# Amplifiers_DAC.net
KiCad netlist of a schematic drawn in Altium Designer
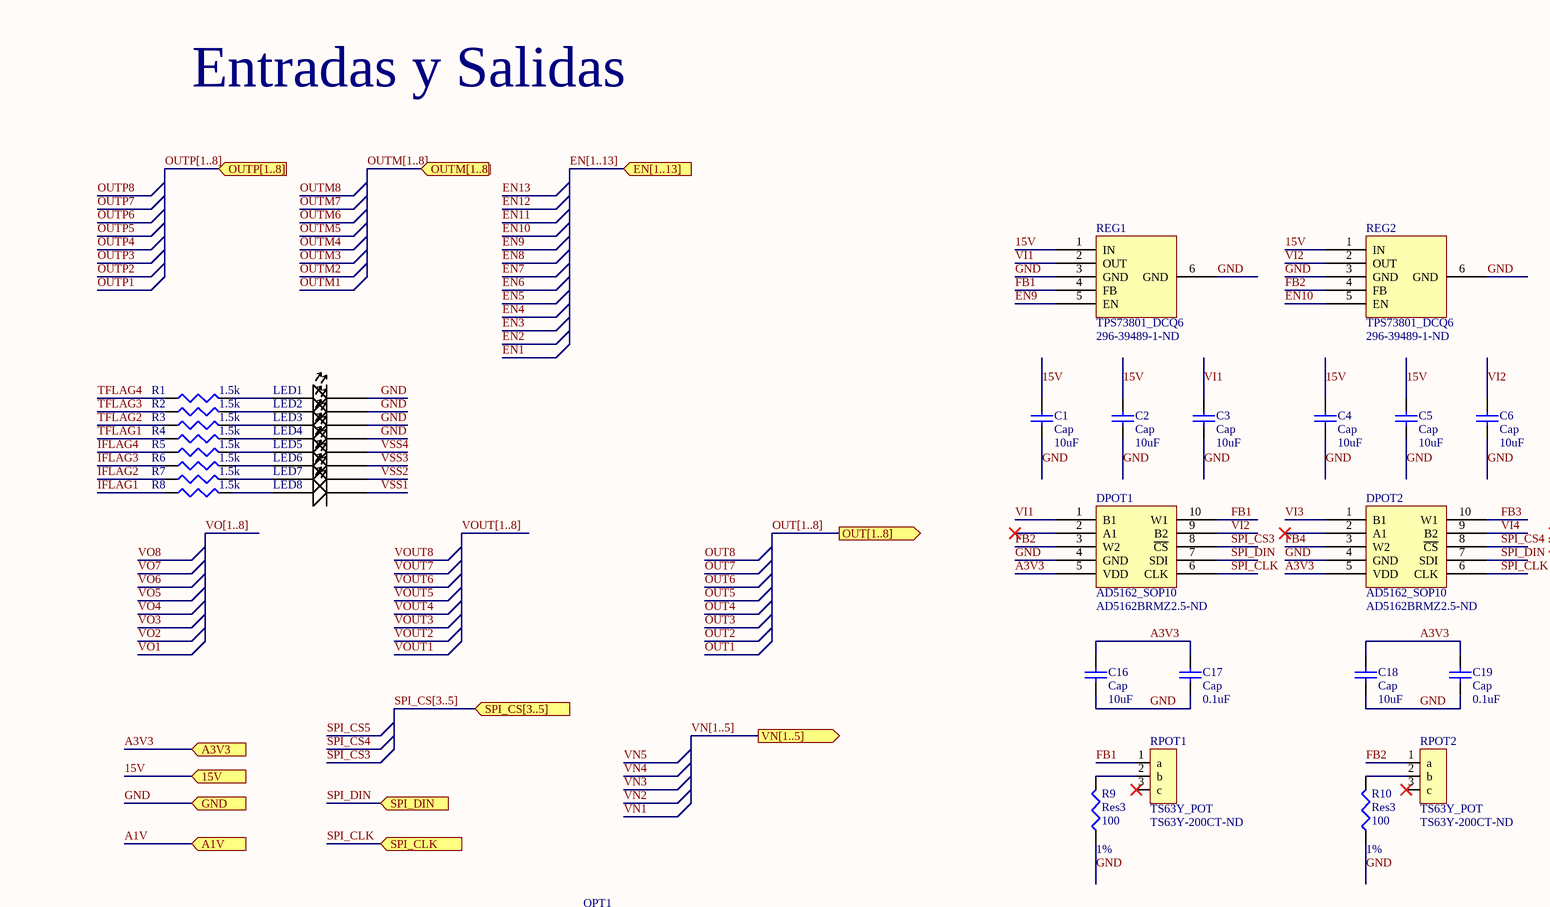
[diagram p0: Amplifiers_DAC.SchDoc, top left]
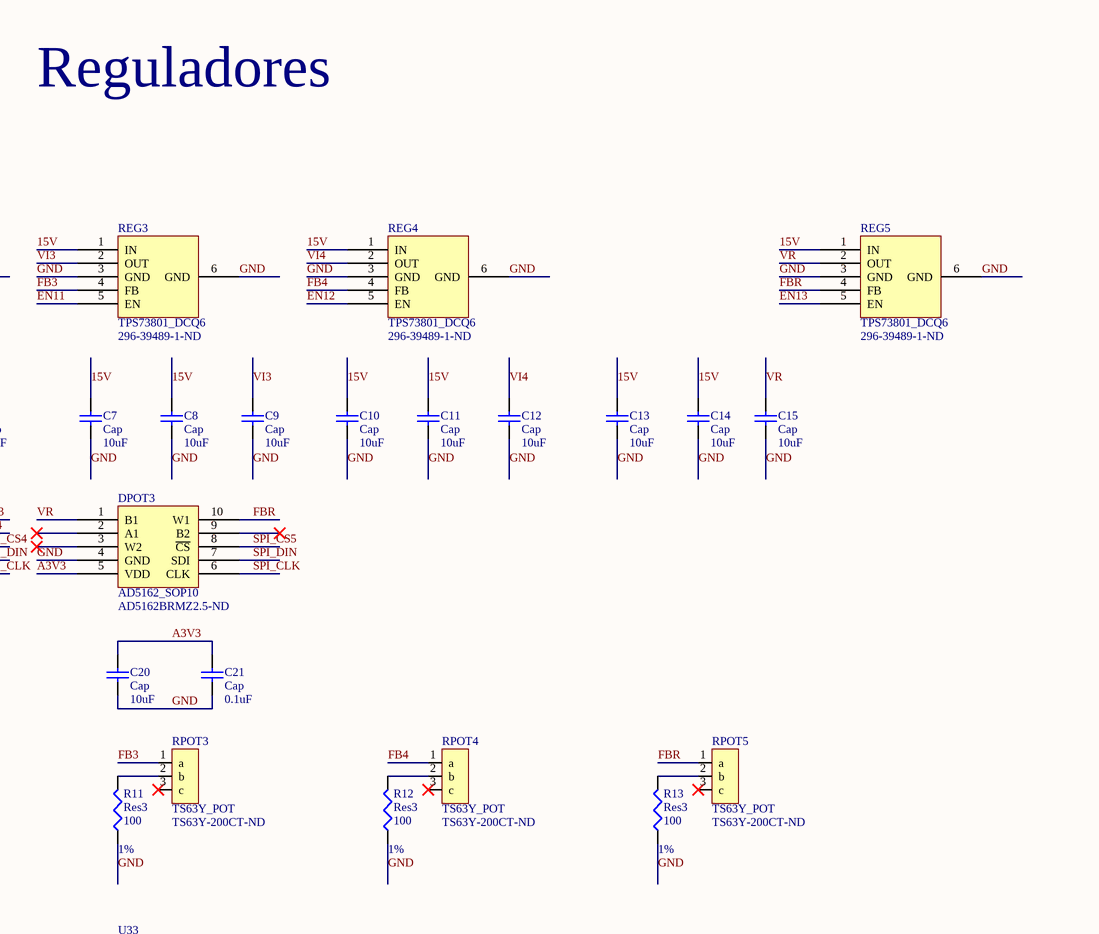
[diagram p1: Amplifiers_DAC.SchDoc, top right]
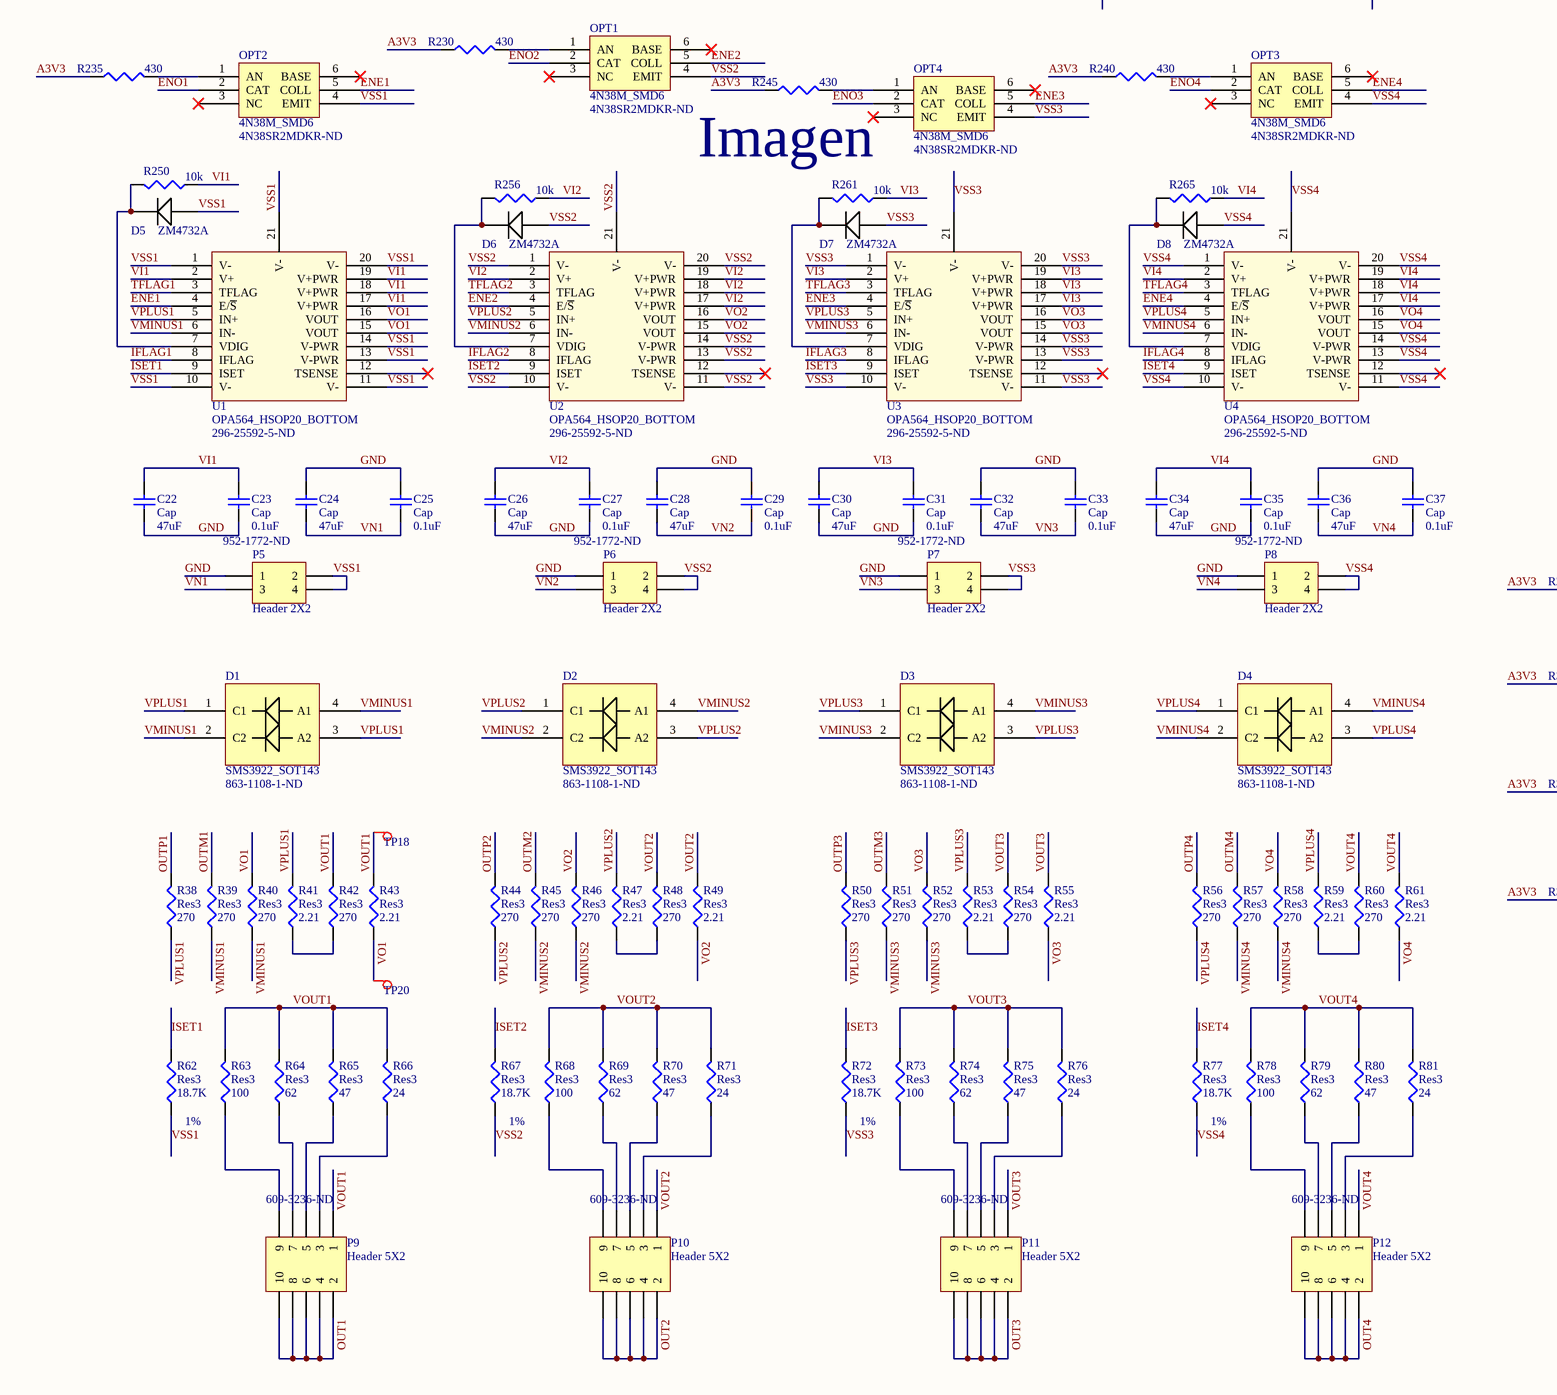
[diagram p2: Amplifiers_DAC.SchDoc, bottom left]
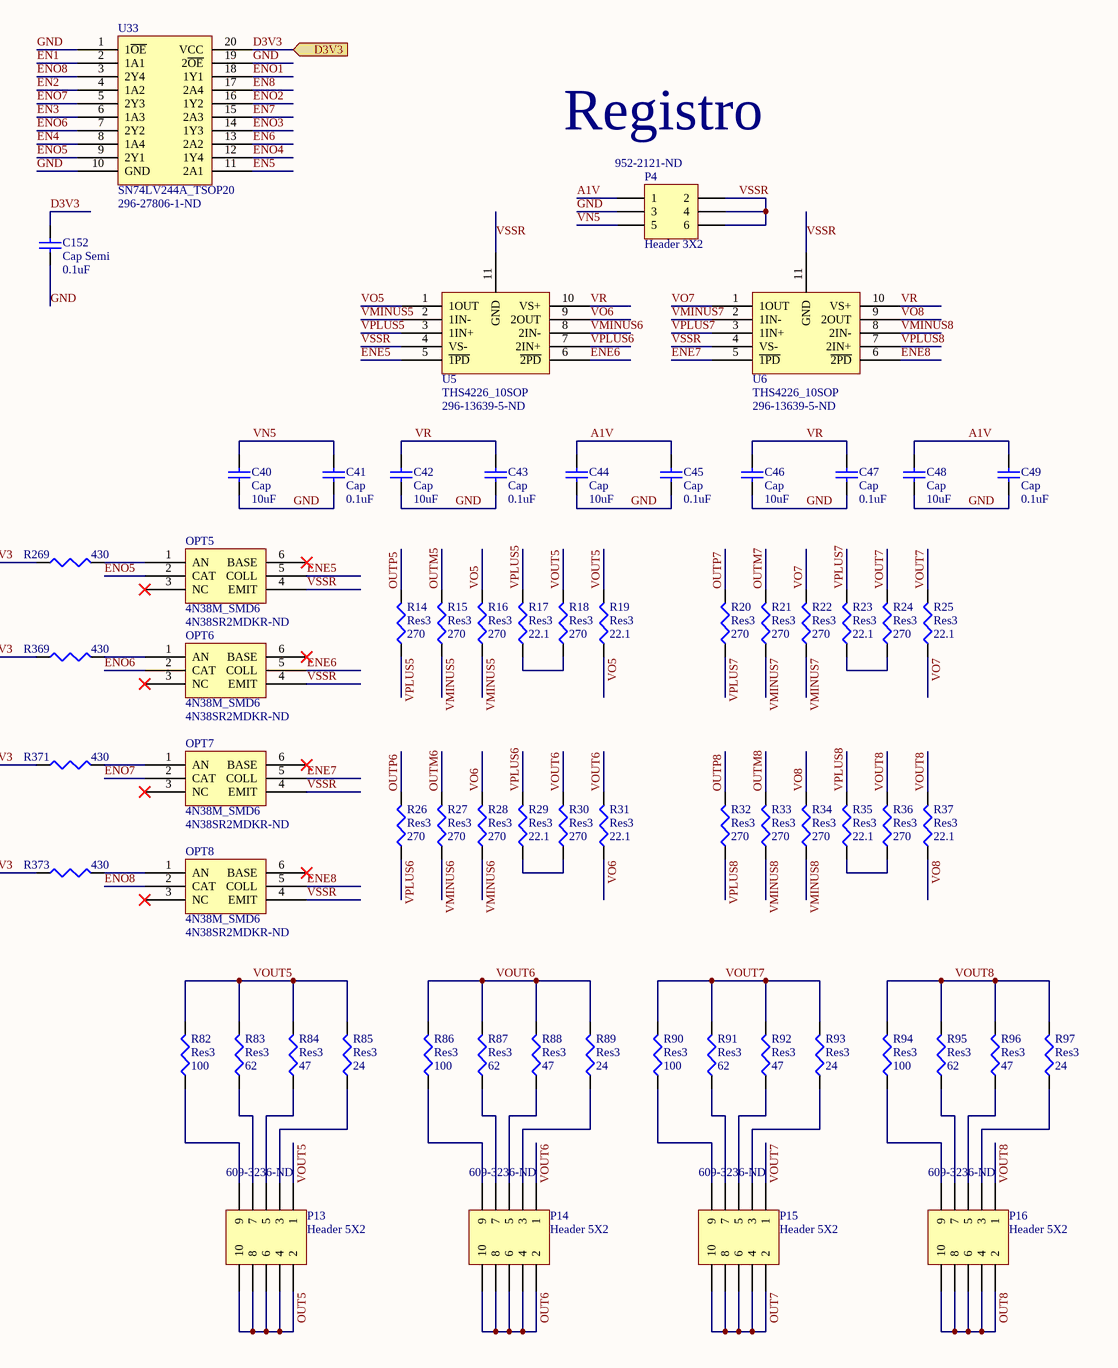
[diagram p3: Amplifiers_DAC.SchDoc, bottom right]

(export (version "E")
  (design (tool "Eeschema 10.0.6"))
  (components
    (comp (ref "C1")
      (value "Cap")
      (footprint "RES_0805")
      (description "Capacitor (Semiconductor SIM Model)")
      (fields (field (name "ALTIUM_VALUE") "10uF") (field (name "PUBLISHER") "Altium Limited"))
      (libsource (lib "Miscellaneous Devices") (part "Cap Semi"))
    )
    (comp (ref "C2")
      (value "Cap")
      (footprint "RES_0805")
      (description "Capacitor (Semiconductor SIM Model)")
      (fields (field (name "ALTIUM_VALUE") "10uF") (field (name "PUBLISHER") "Altium Limited"))
      (libsource (lib "Miscellaneous Devices") (part "Cap Semi"))
    )
    (comp (ref "C3")
      (value "Cap")
      (footprint "RES_0805")
      (description "Capacitor (Semiconductor SIM Model)")
      (fields (field (name "ALTIUM_VALUE") "10uF") (field (name "PUBLISHER") "Altium Limited"))
      (libsource (lib "Miscellaneous Devices") (part "Cap Semi"))
    )
    (comp (ref "C4")
      (value "Cap")
      (footprint "RES_0805")
      (description "Capacitor (Semiconductor SIM Model)")
      (fields (field (name "ALTIUM_VALUE") "10uF") (field (name "PUBLISHER") "Altium Limited"))
      (libsource (lib "Miscellaneous Devices") (part "Cap Semi"))
    )
    (comp (ref "C5")
      (value "Cap")
      (footprint "RES_0805")
      (description "Capacitor (Semiconductor SIM Model)")
      (fields (field (name "ALTIUM_VALUE") "10uF") (field (name "PUBLISHER") "Altium Limited"))
      (libsource (lib "Miscellaneous Devices") (part "Cap Semi"))
    )
    (comp (ref "C6")
      (value "Cap")
      (footprint "RES_0805")
      (description "Capacitor (Semiconductor SIM Model)")
      (fields (field (name "ALTIUM_VALUE") "10uF") (field (name "PUBLISHER") "Altium Limited"))
      (libsource (lib "Miscellaneous Devices") (part "Cap Semi"))
    )
    (comp (ref "C7")
      (value "Cap")
      (footprint "RES_0805")
      (description "Capacitor (Semiconductor SIM Model)")
      (fields (field (name "ALTIUM_VALUE") "10uF") (field (name "PUBLISHER") "Altium Limited"))
      (libsource (lib "Miscellaneous Devices") (part "Cap Semi"))
    )
    (comp (ref "C8")
      (value "Cap")
      (footprint "RES_0805")
      (description "Capacitor (Semiconductor SIM Model)")
      (fields (field (name "ALTIUM_VALUE") "10uF") (field (name "PUBLISHER") "Altium Limited"))
      (libsource (lib "Miscellaneous Devices") (part "Cap Semi"))
    )
    (comp (ref "C9")
      (value "Cap")
      (footprint "RES_0805")
      (description "Capacitor (Semiconductor SIM Model)")
      (fields (field (name "ALTIUM_VALUE") "10uF") (field (name "PUBLISHER") "Altium Limited"))
      (libsource (lib "Miscellaneous Devices") (part "Cap Semi"))
    )
    (comp (ref "C10")
      (value "Cap")
      (footprint "RES_0805")
      (description "Capacitor (Semiconductor SIM Model)")
      (fields (field (name "ALTIUM_VALUE") "10uF") (field (name "PUBLISHER") "Altium Limited"))
      (libsource (lib "Miscellaneous Devices") (part "Cap Semi"))
    )
    (comp (ref "C11")
      (value "Cap")
      (footprint "RES_0805")
      (description "Capacitor (Semiconductor SIM Model)")
      (fields (field (name "ALTIUM_VALUE") "10uF") (field (name "PUBLISHER") "Altium Limited"))
      (libsource (lib "Miscellaneous Devices") (part "Cap Semi"))
    )
    (comp (ref "C12")
      (value "Cap")
      (footprint "RES_0805")
      (description "Capacitor (Semiconductor SIM Model)")
      (fields (field (name "ALTIUM_VALUE") "10uF") (field (name "PUBLISHER") "Altium Limited"))
      (libsource (lib "Miscellaneous Devices") (part "Cap Semi"))
    )
    (comp (ref "C13")
      (value "Cap")
      (footprint "RES_0805")
      (description "Capacitor (Semiconductor SIM Model)")
      (fields (field (name "ALTIUM_VALUE") "10uF") (field (name "PUBLISHER") "Altium Limited"))
      (libsource (lib "Miscellaneous Devices") (part "Cap Semi"))
    )
    (comp (ref "C14")
      (value "Cap")
      (footprint "RES_0805")
      (description "Capacitor (Semiconductor SIM Model)")
      (fields (field (name "ALTIUM_VALUE") "10uF") (field (name "PUBLISHER") "Altium Limited"))
      (libsource (lib "Miscellaneous Devices") (part "Cap Semi"))
    )
    (comp (ref "C15")
      (value "Cap")
      (footprint "RES_0805")
      (description "Capacitor (Semiconductor SIM Model)")
      (fields (field (name "ALTIUM_VALUE") "10uF") (field (name "PUBLISHER") "Altium Limited"))
      (libsource (lib "Miscellaneous Devices") (part "Cap Semi"))
    )
    (comp (ref "C16")
      (value "Cap")
      (footprint "RES_0805")
      (description "Capacitor (Semiconductor SIM Model)")
      (fields (field (name "ALTIUM_VALUE") "10uF") (field (name "PUBLISHER") "Altium Limited"))
      (libsource (lib "Miscellaneous Devices") (part "Cap Semi"))
    )
    (comp (ref "C17")
      (value "Cap")
      (footprint "J1-0603")
      (description "Capacitor (Semiconductor SIM Model)")
      (fields (field (name "ALTIUM_VALUE") "0.1uF") (field (name "PUBLISHER") "Altium Limited"))
      (libsource (lib "Miscellaneous Devices") (part "Cap Semi"))
    )
    (comp (ref "C18")
      (value "Cap")
      (footprint "RES_0805")
      (description "Capacitor (Semiconductor SIM Model)")
      (fields (field (name "ALTIUM_VALUE") "10uF") (field (name "PUBLISHER") "Altium Limited"))
      (libsource (lib "Miscellaneous Devices") (part "Cap Semi"))
    )
    (comp (ref "C19")
      (value "Cap")
      (footprint "J1-0603")
      (description "Capacitor (Semiconductor SIM Model)")
      (fields (field (name "ALTIUM_VALUE") "0.1uF") (field (name "PUBLISHER") "Altium Limited"))
      (libsource (lib "Miscellaneous Devices") (part "Cap Semi"))
    )
    (comp (ref "C20")
      (value "Cap")
      (footprint "RES_0805")
      (description "Capacitor (Semiconductor SIM Model)")
      (fields (field (name "ALTIUM_VALUE") "10uF") (field (name "PUBLISHER") "Altium Limited"))
      (libsource (lib "Miscellaneous Devices") (part "Cap Semi"))
    )
    (comp (ref "C21")
      (value "Cap")
      (footprint "J1-0603")
      (description "Capacitor (Semiconductor SIM Model)")
      (fields (field (name "ALTIUM_VALUE") "0.1uF") (field (name "PUBLISHER") "Altium Limited"))
      (libsource (lib "Miscellaneous Devices") (part "Cap Semi"))
    )
    (comp (ref "C22")
      (value "Cap")
      (footprint "RES_1206")
      (description "Capacitor (Semiconductor SIM Model)")
      (fields (field (name "ALTIUM_VALUE") "47uF") (field (name "PUBLISHER") "Altium Limited"))
      (libsource (lib "Miscellaneous Devices") (part "Cap Semi"))
    )
    (comp (ref "C23")
      (value "Cap")
      (footprint "J1-0603")
      (description "Capacitor (Semiconductor SIM Model)")
      (fields (field (name "ALTIUM_VALUE") "0.1uF") (field (name "PUBLISHER") "Altium Limited"))
      (libsource (lib "Miscellaneous Devices") (part "Cap Semi"))
    )
    (comp (ref "C24")
      (value "Cap")
      (footprint "RES_1206")
      (description "Capacitor (Semiconductor SIM Model)")
      (fields (field (name "ALTIUM_VALUE") "47uF") (field (name "PUBLISHER") "Altium Limited"))
      (libsource (lib "Miscellaneous Devices") (part "Cap Semi"))
    )
    (comp (ref "C25")
      (value "Cap")
      (footprint "J1-0603")
      (description "Capacitor (Semiconductor SIM Model)")
      (fields (field (name "ALTIUM_VALUE") "0.1uF") (field (name "PUBLISHER") "Altium Limited"))
      (libsource (lib "Miscellaneous Devices") (part "Cap Semi"))
    )
    (comp (ref "C26")
      (value "Cap")
      (footprint "RES_1206")
      (description "Capacitor (Semiconductor SIM Model)")
      (fields (field (name "ALTIUM_VALUE") "47uF") (field (name "PUBLISHER") "Altium Limited"))
      (libsource (lib "Miscellaneous Devices") (part "Cap Semi"))
    )
    (comp (ref "C27")
      (value "Cap")
      (footprint "J1-0603")
      (description "Capacitor (Semiconductor SIM Model)")
      (fields (field (name "ALTIUM_VALUE") "0.1uF") (field (name "PUBLISHER") "Altium Limited"))
      (libsource (lib "Miscellaneous Devices") (part "Cap Semi"))
    )
    (comp (ref "C28")
      (value "Cap")
      (footprint "RES_1206")
      (description "Capacitor (Semiconductor SIM Model)")
      (fields (field (name "ALTIUM_VALUE") "47uF") (field (name "PUBLISHER") "Altium Limited"))
      (libsource (lib "Miscellaneous Devices") (part "Cap Semi"))
    )
    (comp (ref "C29")
      (value "Cap")
      (footprint "J1-0603")
      (description "Capacitor (Semiconductor SIM Model)")
      (fields (field (name "ALTIUM_VALUE") "0.1uF") (field (name "PUBLISHER") "Altium Limited"))
      (libsource (lib "Miscellaneous Devices") (part "Cap Semi"))
    )
    (comp (ref "C30")
      (value "Cap")
      (footprint "RES_1206")
      (description "Capacitor (Semiconductor SIM Model)")
      (fields (field (name "ALTIUM_VALUE") "47uF") (field (name "PUBLISHER") "Altium Limited"))
      (libsource (lib "Miscellaneous Devices") (part "Cap Semi"))
    )
    (comp (ref "C31")
      (value "Cap")
      (footprint "J1-0603")
      (description "Capacitor (Semiconductor SIM Model)")
      (fields (field (name "ALTIUM_VALUE") "0.1uF") (field (name "PUBLISHER") "Altium Limited"))
      (libsource (lib "Miscellaneous Devices") (part "Cap Semi"))
    )
    (comp (ref "C32")
      (value "Cap")
      (footprint "RES_1206")
      (description "Capacitor (Semiconductor SIM Model)")
      (fields (field (name "ALTIUM_VALUE") "47uF") (field (name "PUBLISHER") "Altium Limited"))
      (libsource (lib "Miscellaneous Devices") (part "Cap Semi"))
    )
    (comp (ref "C33")
      (value "Cap")
      (footprint "J1-0603")
      (description "Capacitor (Semiconductor SIM Model)")
      (fields (field (name "ALTIUM_VALUE") "0.1uF") (field (name "PUBLISHER") "Altium Limited"))
      (libsource (lib "Miscellaneous Devices") (part "Cap Semi"))
    )
    (comp (ref "C34")
      (value "Cap")
      (footprint "RES_1206")
      (description "Capacitor (Semiconductor SIM Model)")
      (fields (field (name "ALTIUM_VALUE") "47uF") (field (name "PUBLISHER") "Altium Limited"))
      (libsource (lib "Miscellaneous Devices") (part "Cap Semi"))
    )
    (comp (ref "C35")
      (value "Cap")
      (footprint "J1-0603")
      (description "Capacitor (Semiconductor SIM Model)")
      (fields (field (name "ALTIUM_VALUE") "0.1uF") (field (name "PUBLISHER") "Altium Limited"))
      (libsource (lib "Miscellaneous Devices") (part "Cap Semi"))
    )
    (comp (ref "C36")
      (value "Cap")
      (footprint "RES_1206")
      (description "Capacitor (Semiconductor SIM Model)")
      (fields (field (name "ALTIUM_VALUE") "47uF") (field (name "PUBLISHER") "Altium Limited"))
      (libsource (lib "Miscellaneous Devices") (part "Cap Semi"))
    )
    (comp (ref "C37")
      (value "Cap")
      (footprint "J1-0603")
      (description "Capacitor (Semiconductor SIM Model)")
      (fields (field (name "ALTIUM_VALUE") "0.1uF") (field (name "PUBLISHER") "Altium Limited"))
      (libsource (lib "Miscellaneous Devices") (part "Cap Semi"))
    )
    (comp (ref "C40")
      (value "Cap")
      (footprint "RES_0805")
      (description "Capacitor (Semiconductor SIM Model)")
      (fields (field (name "ALTIUM_VALUE") "10uF") (field (name "PUBLISHER") "Altium Limited"))
      (libsource (lib "Miscellaneous Devices") (part "Cap Semi"))
    )
    (comp (ref "C41")
      (value "Cap")
      (footprint "J1-0603")
      (description "Capacitor (Semiconductor SIM Model)")
      (fields (field (name "ALTIUM_VALUE") "0.1uF") (field (name "PUBLISHER") "Altium Limited"))
      (libsource (lib "Miscellaneous Devices") (part "Cap Semi"))
    )
    (comp (ref "C42")
      (value "Cap")
      (footprint "RES_0805")
      (description "Capacitor (Semiconductor SIM Model)")
      (fields (field (name "ALTIUM_VALUE") "10uF") (field (name "PUBLISHER") "Altium Limited"))
      (libsource (lib "Miscellaneous Devices") (part "Cap Semi"))
    )
    (comp (ref "C43")
      (value "Cap")
      (footprint "J1-0603")
      (description "Capacitor (Semiconductor SIM Model)")
      (fields (field (name "ALTIUM_VALUE") "0.1uF") (field (name "PUBLISHER") "Altium Limited"))
      (libsource (lib "Miscellaneous Devices") (part "Cap Semi"))
    )
    (comp (ref "C44")
      (value "Cap")
      (footprint "RES_0805")
      (description "Capacitor (Semiconductor SIM Model)")
      (fields (field (name "ALTIUM_VALUE") "10uF") (field (name "PUBLISHER") "Altium Limited"))
      (libsource (lib "Miscellaneous Devices") (part "Cap Semi"))
    )
    (comp (ref "C45")
      (value "Cap")
      (footprint "J1-0603")
      (description "Capacitor (Semiconductor SIM Model)")
      (fields (field (name "ALTIUM_VALUE") "0.1uF") (field (name "PUBLISHER") "Altium Limited"))
      (libsource (lib "Miscellaneous Devices") (part "Cap Semi"))
    )
    (comp (ref "C46")
      (value "Cap")
      (footprint "RES_0805")
      (description "Capacitor (Semiconductor SIM Model)")
      (fields (field (name "ALTIUM_VALUE") "10uF") (field (name "PUBLISHER") "Altium Limited"))
      (libsource (lib "Miscellaneous Devices") (part "Cap Semi"))
    )
    (comp (ref "C47")
      (value "Cap")
      (footprint "J1-0603")
      (description "Capacitor (Semiconductor SIM Model)")
      (fields (field (name "ALTIUM_VALUE") "0.1uF") (field (name "PUBLISHER") "Altium Limited"))
      (libsource (lib "Miscellaneous Devices") (part "Cap Semi"))
    )
    (comp (ref "C48")
      (value "Cap")
      (footprint "RES_0805")
      (description "Capacitor (Semiconductor SIM Model)")
      (fields (field (name "ALTIUM_VALUE") "10uF") (field (name "PUBLISHER") "Altium Limited"))
      (libsource (lib "Miscellaneous Devices") (part "Cap Semi"))
    )
    (comp (ref "C49")
      (value "Cap")
      (footprint "J1-0603")
      (description "Capacitor (Semiconductor SIM Model)")
      (fields (field (name "ALTIUM_VALUE") "0.1uF") (field (name "PUBLISHER") "Altium Limited"))
      (libsource (lib "Miscellaneous Devices") (part "Cap Semi"))
    )
    (comp (ref "C152")
      (value "Cap Semi")
      (footprint "J1-0603")
      (description "Capacitor (Semiconductor SIM Model)")
      (fields (field (name "ALTIUM_VALUE") "0.1uF") (field (name "PUBLISHER") "Altium Limited"))
      (libsource (lib "Miscellaneous Devices") (part "Cap Semi"))
    )
    (comp (ref "D1")
      (value "SMS3922_SOT143")
      (footprint "SMS3922_SOT143")
      (fields (field (name "SUPPLIER PART NUMBER 1") "863-1108-1-ND"))
      (libsource (lib "Lib1") (part "SMS3922_SOT143"))
    )
    (comp (ref "D2")
      (value "SMS3922_SOT143")
      (footprint "SMS3922_SOT143")
      (fields (field (name "SUPPLIER PART NUMBER 1") "863-1108-1-ND"))
      (libsource (lib "Lib1") (part "SMS3922_SOT143"))
    )
    (comp (ref "D3")
      (value "SMS3922_SOT143")
      (footprint "SMS3922_SOT143")
      (fields (field (name "SUPPLIER PART NUMBER 1") "863-1108-1-ND"))
      (libsource (lib "Lib1") (part "SMS3922_SOT143"))
    )
    (comp (ref "D4")
      (value "SMS3922_SOT143")
      (footprint "SMS3922_SOT143")
      (fields (field (name "SUPPLIER PART NUMBER 1") "863-1108-1-ND"))
      (libsource (lib "Lib1") (part "SMS3922_SOT143"))
    )
    (comp (ref "D5") (value "ZM4732A") (footprint "ZM4732A") (libsource (lib "Lib1") (part "ZM4732A")))
    (comp (ref "D6") (value "ZM4732A") (footprint "ZM4732A") (libsource (lib "Lib1") (part "ZM4732A")))
    (comp (ref "D7") (value "ZM4732A") (footprint "ZM4732A") (libsource (lib "Lib1") (part "ZM4732A")))
    (comp (ref "D8") (value "ZM4732A") (footprint "ZM4732A") (libsource (lib "Lib1") (part "ZM4732A")))
    (comp (ref "DPOT1")
      (value "AD5162_SOP10")
      (footprint "AD5162_SOP10")
      (fields (field (name "SUPPLIER PART NUMBER 1") "AD5162BRMZ2.5-ND"))
      (libsource (lib "Lib1") (part "AD5162_SOP10"))
    )
    (comp (ref "DPOT2")
      (value "AD5162_SOP10")
      (footprint "AD5162_SOP10")
      (fields (field (name "SUPPLIER PART NUMBER 1") "AD5162BRMZ2.5-ND"))
      (libsource (lib "Lib1") (part "AD5162_SOP10"))
    )
    (comp (ref "DPOT3")
      (value "AD5162_SOP10")
      (footprint "AD5162_SOP10")
      (fields (field (name "SUPPLIER PART NUMBER 1") "AD5162BRMZ2.5-ND"))
      (libsource (lib "Lib1") (part "AD5162_SOP10"))
    )
    (comp (ref "LED1") (value "LED") (footprint "LED") (libsource (lib "Lib1") (part "LED")))
    (comp (ref "LED2") (value "LED") (footprint "LED") (libsource (lib "Lib1") (part "LED")))
    (comp (ref "LED3") (value "LED") (footprint "LED") (libsource (lib "Lib1") (part "LED")))
    (comp (ref "LED4") (value "LED") (footprint "LED") (libsource (lib "Lib1") (part "LED")))
    (comp (ref "LED5") (value "LED") (footprint "LED") (libsource (lib "Lib1") (part "LED")))
    (comp (ref "LED6") (value "LED") (footprint "LED") (libsource (lib "Lib1") (part "LED")))
    (comp (ref "LED7") (value "LED") (footprint "LED") (libsource (lib "Lib1") (part "LED")))
    (comp (ref "LED8") (value "LED") (footprint "LED") (libsource (lib "Lib1") (part "LED")))
    (comp (ref "OPT1")
      (value "4N38M_SMD6")
      (footprint "4N38M_SMD6")
      (fields (field (name "SUPPLIER PART NUMBER 1") "4N38SR2MDKR-ND"))
      (libsource (lib "Lib1") (part "4N38M_SMD6"))
    )
    (comp (ref "OPT2")
      (value "4N38M_SMD6")
      (footprint "4N38M_SMD6")
      (fields (field (name "SUPPLIER PART NUMBER 1") "4N38SR2MDKR-ND"))
      (libsource (lib "Lib1") (part "4N38M_SMD6"))
    )
    (comp (ref "OPT3")
      (value "4N38M_SMD6")
      (footprint "4N38M_SMD6")
      (fields (field (name "SUPPLIER PART NUMBER 1") "4N38SR2MDKR-ND"))
      (libsource (lib "Lib1") (part "4N38M_SMD6"))
    )
    (comp (ref "OPT4")
      (value "4N38M_SMD6")
      (footprint "4N38M_SMD6")
      (fields (field (name "SUPPLIER PART NUMBER 1") "4N38SR2MDKR-ND"))
      (libsource (lib "Lib1") (part "4N38M_SMD6"))
    )
    (comp (ref "OPT5")
      (value "4N38M_SMD6")
      (footprint "4N38M_SMD6")
      (fields (field (name "SUPPLIER PART NUMBER 1") "4N38SR2MDKR-ND"))
      (libsource (lib "Lib1") (part "4N38M_SMD6"))
    )
    (comp (ref "OPT6")
      (value "4N38M_SMD6")
      (footprint "4N38M_SMD6")
      (fields (field (name "SUPPLIER PART NUMBER 1") "4N38SR2MDKR-ND"))
      (libsource (lib "Lib1") (part "4N38M_SMD6"))
    )
    (comp (ref "OPT7")
      (value "4N38M_SMD6")
      (footprint "4N38M_SMD6")
      (fields (field (name "SUPPLIER PART NUMBER 1") "4N38SR2MDKR-ND"))
      (libsource (lib "Lib1") (part "4N38M_SMD6"))
    )
    (comp (ref "OPT8")
      (value "4N38M_SMD6")
      (footprint "4N38M_SMD6")
      (fields (field (name "SUPPLIER PART NUMBER 1") "4N38SR2MDKR-ND"))
      (libsource (lib "Lib1") (part "4N38M_SMD6"))
    )
    (comp (ref "P4")
      (value "Header 3X2")
      (footprint "HDR2X3")
      (description "Header, 3-Pin, Dual row")
      (fields
        (field (name "SUPPLIER PART NUMBER 1") "952-2121-ND")
        (field (name "PUBLISHER") "Altium Limited")
      )
      (libsource (lib "Miscellaneous Connectors") (part "Header 3X2"))
    )
    (comp (ref "P5")
      (value "Header 2X2")
      (footprint "HDR2X2")
      (description "Header, 2-Pin, Dual row")
      (fields
        (field (name "SUPPLIER PART NUMBER 1") "952-1772-ND")
        (field (name "PUBLISHER") "Altium Limited")
      )
      (libsource (lib "Miscellaneous Connectors") (part "Header 2X2"))
    )
    (comp (ref "P6")
      (value "Header 2X2")
      (footprint "HDR2X2")
      (description "Header, 2-Pin, Dual row")
      (fields
        (field (name "SUPPLIER PART NUMBER 1") "952-1772-ND")
        (field (name "PUBLISHER") "Altium Limited")
      )
      (libsource (lib "Miscellaneous Connectors") (part "Header 2X2"))
    )
    (comp (ref "P7")
      (value "Header 2X2")
      (footprint "HDR2X2")
      (description "Header, 2-Pin, Dual row")
      (fields
        (field (name "SUPPLIER PART NUMBER 1") "952-1772-ND")
        (field (name "PUBLISHER") "Altium Limited")
      )
      (libsource (lib "Miscellaneous Connectors") (part "Header 2X2"))
    )
    (comp (ref "P8")
      (value "Header 2X2")
      (footprint "HDR2X2")
      (description "Header, 2-Pin, Dual row")
      (fields
        (field (name "SUPPLIER PART NUMBER 1") "952-1772-ND")
        (field (name "PUBLISHER") "Altium Limited")
      )
      (libsource (lib "Miscellaneous Connectors") (part "Header 2X2"))
    )
    (comp (ref "P9")
      (value "Header 5X2")
      (footprint "HDR2X5")
      (description "Header, 5-Pin, Dual row")
      (fields
        (field (name "SUPPLIER PART NUMBER 1") "609-3236-ND")
        (field (name "PUBLISHER") "Altium Limited")
      )
      (libsource (lib "Miscellaneous Connectors") (part "Header 5X2"))
    )
    (comp (ref "P10")
      (value "Header 5X2")
      (footprint "HDR2X5")
      (description "Header, 5-Pin, Dual row")
      (fields
        (field (name "SUPPLIER PART NUMBER 1") "609-3236-ND")
        (field (name "PUBLISHER") "Altium Limited")
      )
      (libsource (lib "Miscellaneous Connectors") (part "Header 5X2"))
    )
    (comp (ref "P11")
      (value "Header 5X2")
      (footprint "HDR2X5")
      (description "Header, 5-Pin, Dual row")
      (fields
        (field (name "SUPPLIER PART NUMBER 1") "609-3236-ND")
        (field (name "PUBLISHER") "Altium Limited")
      )
      (libsource (lib "Miscellaneous Connectors") (part "Header 5X2"))
    )
    (comp (ref "P12")
      (value "Header 5X2")
      (footprint "HDR2X5")
      (description "Header, 5-Pin, Dual row")
      (fields
        (field (name "SUPPLIER PART NUMBER 1") "609-3236-ND")
        (field (name "PUBLISHER") "Altium Limited")
      )
      (libsource (lib "Miscellaneous Connectors") (part "Header 5X2"))
    )
    (comp (ref "P13")
      (value "Header 5X2")
      (footprint "HDR2X5")
      (description "Header, 5-Pin, Dual row")
      (fields
        (field (name "SUPPLIER PART NUMBER 1") "609-3236-ND")
        (field (name "PUBLISHER") "Altium Limited")
      )
      (libsource (lib "Miscellaneous Connectors") (part "Header 5X2"))
    )
    (comp (ref "P14")
      (value "Header 5X2")
      (footprint "HDR2X5")
      (description "Header, 5-Pin, Dual row")
      (fields
        (field (name "SUPPLIER PART NUMBER 1") "609-3236-ND")
        (field (name "PUBLISHER") "Altium Limited")
      )
      (libsource (lib "Miscellaneous Connectors") (part "Header 5X2"))
    )
    (comp (ref "P15")
      (value "Header 5X2")
      (footprint "HDR2X5")
      (description "Header, 5-Pin, Dual row")
      (fields
        (field (name "SUPPLIER PART NUMBER 1") "609-3236-ND")
        (field (name "PUBLISHER") "Altium Limited")
      )
      (libsource (lib "Miscellaneous Connectors") (part "Header 5X2"))
    )
    (comp (ref "P16")
      (value "Header 5X2")
      (footprint "HDR2X5")
      (description "Header, 5-Pin, Dual row")
      (fields
        (field (name "SUPPLIER PART NUMBER 1") "609-3236-ND")
        (field (name "PUBLISHER") "Altium Limited")
      )
      (libsource (lib "Miscellaneous Connectors") (part "Header 5X2"))
    )
    (comp (ref "R1")
      (value "1.5k")
      (footprint "J1-0603")
      (description "Resistor")
      (fields (field (name "Comment") "Res3") (field (name "PUBLISHER") "Altium Limited"))
      (libsource (lib "Miscellaneous Devices") (part "Res3"))
    )
    (comp (ref "R2")
      (value "1.5k")
      (footprint "J1-0603")
      (description "Resistor")
      (fields (field (name "Comment") "Res3") (field (name "PUBLISHER") "Altium Limited"))
      (libsource (lib "Miscellaneous Devices") (part "Res3"))
    )
    (comp (ref "R3")
      (value "1.5k")
      (footprint "J1-0603")
      (description "Resistor")
      (fields (field (name "Comment") "Res3") (field (name "PUBLISHER") "Altium Limited"))
      (libsource (lib "Miscellaneous Devices") (part "Res3"))
    )
    (comp (ref "R4")
      (value "1.5k")
      (footprint "J1-0603")
      (description "Resistor")
      (fields (field (name "Comment") "Res3") (field (name "PUBLISHER") "Altium Limited"))
      (libsource (lib "Miscellaneous Devices") (part "Res3"))
    )
    (comp (ref "R5")
      (value "1.5k")
      (footprint "J1-0603")
      (description "Resistor")
      (fields (field (name "Comment") "Res3") (field (name "PUBLISHER") "Altium Limited"))
      (libsource (lib "Miscellaneous Devices") (part "Res3"))
    )
    (comp (ref "R6")
      (value "1.5k")
      (footprint "J1-0603")
      (description "Resistor")
      (fields (field (name "Comment") "Res3") (field (name "PUBLISHER") "Altium Limited"))
      (libsource (lib "Miscellaneous Devices") (part "Res3"))
    )
    (comp (ref "R7")
      (value "1.5k")
      (footprint "J1-0603")
      (description "Resistor")
      (fields (field (name "Comment") "Res3") (field (name "PUBLISHER") "Altium Limited"))
      (libsource (lib "Miscellaneous Devices") (part "Res3"))
    )
    (comp (ref "R8")
      (value "1.5k")
      (footprint "J1-0603")
      (description "Resistor")
      (fields (field (name "Comment") "Res3") (field (name "PUBLISHER") "Altium Limited"))
      (libsource (lib "Miscellaneous Devices") (part "Res3"))
    )
    (comp (ref "R9")
      (value "Res3")
      (footprint "J1-0603")
      (description "Resistor")
      (fields
        (field (name "ALTIUM_VALUE") "100")
        (field (name "TOL") "1%")
        (field (name "PUBLISHER") "Altium Limited")
      )
      (libsource (lib "Miscellaneous Devices") (part "Res3"))
    )
    (comp (ref "R10")
      (value "Res3")
      (footprint "J1-0603")
      (description "Resistor")
      (fields
        (field (name "ALTIUM_VALUE") "100")
        (field (name "TOL") "1%")
        (field (name "PUBLISHER") "Altium Limited")
      )
      (libsource (lib "Miscellaneous Devices") (part "Res3"))
    )
    (comp (ref "R11")
      (value "Res3")
      (footprint "J1-0603")
      (description "Resistor")
      (fields
        (field (name "ALTIUM_VALUE") "100")
        (field (name "TOL") "1%")
        (field (name "PUBLISHER") "Altium Limited")
      )
      (libsource (lib "Miscellaneous Devices") (part "Res3"))
    )
    (comp (ref "R12")
      (value "Res3")
      (footprint "J1-0603")
      (description "Resistor")
      (fields
        (field (name "ALTIUM_VALUE") "100")
        (field (name "TOL") "1%")
        (field (name "PUBLISHER") "Altium Limited")
      )
      (libsource (lib "Miscellaneous Devices") (part "Res3"))
    )
    (comp (ref "R13")
      (value "Res3")
      (footprint "J1-0603")
      (description "Resistor")
      (fields
        (field (name "ALTIUM_VALUE") "100")
        (field (name "TOL") "1%")
        (field (name "PUBLISHER") "Altium Limited")
      )
      (libsource (lib "Miscellaneous Devices") (part "Res3"))
    )
    (comp (ref "R14")
      (value "Res3")
      (footprint "RES_1206")
      (description "Resistor")
      (fields (field (name "ALTIUM_VALUE") "270") (field (name "PUBLISHER") "Altium Limited"))
      (libsource (lib "Miscellaneous Devices") (part "Res3"))
    )
    (comp (ref "R15")
      (value "Res3")
      (footprint "RES_1206")
      (description "Resistor")
      (fields (field (name "ALTIUM_VALUE") "270") (field (name "PUBLISHER") "Altium Limited"))
      (libsource (lib "Miscellaneous Devices") (part "Res3"))
    )
    (comp (ref "R16")
      (value "Res3")
      (footprint "RES_1206")
      (description "Resistor")
      (fields (field (name "ALTIUM_VALUE") "270") (field (name "PUBLISHER") "Altium Limited"))
      (libsource (lib "Miscellaneous Devices") (part "Res3"))
    )
    (comp (ref "R17")
      (value "Res3")
      (footprint "RES_0805")
      (description "Resistor")
      (fields (field (name "ALTIUM_VALUE") "22.1") (field (name "PUBLISHER") "Altium Limited"))
      (libsource (lib "Miscellaneous Devices") (part "Res3"))
    )
    (comp (ref "R18")
      (value "Res3")
      (footprint "RES_1206")
      (description "Resistor")
      (fields (field (name "ALTIUM_VALUE") "270") (field (name "PUBLISHER") "Altium Limited"))
      (libsource (lib "Miscellaneous Devices") (part "Res3"))
    )
    (comp (ref "R19")
      (value "Res3")
      (footprint "RES_0805")
      (description "Resistor")
      (fields (field (name "ALTIUM_VALUE") "22.1") (field (name "PUBLISHER") "Altium Limited"))
      (libsource (lib "Miscellaneous Devices") (part "Res3"))
    )
    (comp (ref "R20")
      (value "Res3")
      (footprint "RES_1206")
      (description "Resistor")
      (fields (field (name "ALTIUM_VALUE") "270") (field (name "PUBLISHER") "Altium Limited"))
      (libsource (lib "Miscellaneous Devices") (part "Res3"))
    )
    (comp (ref "R21")
      (value "Res3")
      (footprint "RES_1206")
      (description "Resistor")
      (fields (field (name "ALTIUM_VALUE") "270") (field (name "PUBLISHER") "Altium Limited"))
      (libsource (lib "Miscellaneous Devices") (part "Res3"))
    )
    (comp (ref "R22")
      (value "Res3")
      (footprint "RES_1206")
      (description "Resistor")
      (fields (field (name "ALTIUM_VALUE") "270") (field (name "PUBLISHER") "Altium Limited"))
      (libsource (lib "Miscellaneous Devices") (part "Res3"))
    )
    (comp (ref "R23")
      (value "Res3")
      (footprint "RES_0805")
      (description "Resistor")
      (fields (field (name "ALTIUM_VALUE") "22.1") (field (name "PUBLISHER") "Altium Limited"))
      (libsource (lib "Miscellaneous Devices") (part "Res3"))
    )
    (comp (ref "R24")
      (value "Res3")
      (footprint "RES_1206")
      (description "Resistor")
      (fields (field (name "ALTIUM_VALUE") "270") (field (name "PUBLISHER") "Altium Limited"))
      (libsource (lib "Miscellaneous Devices") (part "Res3"))
    )
    (comp (ref "R25")
      (value "Res3")
      (footprint "RES_0805")
      (description "Resistor")
      (fields (field (name "ALTIUM_VALUE") "22.1") (field (name "PUBLISHER") "Altium Limited"))
      (libsource (lib "Miscellaneous Devices") (part "Res3"))
    )
    (comp (ref "R26")
      (value "Res3")
      (footprint "RES_1206")
      (description "Resistor")
      (fields (field (name "ALTIUM_VALUE") "270") (field (name "PUBLISHER") "Altium Limited"))
      (libsource (lib "Miscellaneous Devices") (part "Res3"))
    )
    (comp (ref "R27")
      (value "Res3")
      (footprint "RES_1206")
      (description "Resistor")
      (fields (field (name "ALTIUM_VALUE") "270") (field (name "PUBLISHER") "Altium Limited"))
      (libsource (lib "Miscellaneous Devices") (part "Res3"))
    )
    (comp (ref "R28")
      (value "Res3")
      (footprint "RES_1206")
      (description "Resistor")
      (fields (field (name "ALTIUM_VALUE") "270") (field (name "PUBLISHER") "Altium Limited"))
      (libsource (lib "Miscellaneous Devices") (part "Res3"))
    )
    (comp (ref "R29")
      (value "Res3")
      (footprint "RES_0805")
      (description "Resistor")
      (fields (field (name "ALTIUM_VALUE") "22.1") (field (name "PUBLISHER") "Altium Limited"))
      (libsource (lib "Miscellaneous Devices") (part "Res3"))
    )
    (comp (ref "R30")
      (value "Res3")
      (footprint "RES_1206")
      (description "Resistor")
      (fields (field (name "ALTIUM_VALUE") "270") (field (name "PUBLISHER") "Altium Limited"))
      (libsource (lib "Miscellaneous Devices") (part "Res3"))
    )
    (comp (ref "R31")
      (value "Res3")
      (footprint "RES_0805")
      (description "Resistor")
      (fields (field (name "ALTIUM_VALUE") "22.1") (field (name "PUBLISHER") "Altium Limited"))
      (libsource (lib "Miscellaneous Devices") (part "Res3"))
    )
    (comp (ref "R32")
      (value "Res3")
      (footprint "RES_1206")
      (description "Resistor")
      (fields (field (name "ALTIUM_VALUE") "270") (field (name "PUBLISHER") "Altium Limited"))
      (libsource (lib "Miscellaneous Devices") (part "Res3"))
    )
    (comp (ref "R33")
      (value "Res3")
      (footprint "RES_1206")
      (description "Resistor")
      (fields (field (name "ALTIUM_VALUE") "270") (field (name "PUBLISHER") "Altium Limited"))
      (libsource (lib "Miscellaneous Devices") (part "Res3"))
    )
    (comp (ref "R34")
      (value "Res3")
      (footprint "RES_1206")
      (description "Resistor")
      (fields (field (name "ALTIUM_VALUE") "270") (field (name "PUBLISHER") "Altium Limited"))
      (libsource (lib "Miscellaneous Devices") (part "Res3"))
    )
    (comp (ref "R35")
      (value "Res3")
      (footprint "RES_0805")
      (description "Resistor")
      (fields (field (name "ALTIUM_VALUE") "22.1") (field (name "PUBLISHER") "Altium Limited"))
      (libsource (lib "Miscellaneous Devices") (part "Res3"))
    )
    (comp (ref "R36")
      (value "Res3")
      (footprint "RES_1206")
      (description "Resistor")
      (fields (field (name "ALTIUM_VALUE") "270") (field (name "PUBLISHER") "Altium Limited"))
      (libsource (lib "Miscellaneous Devices") (part "Res3"))
    )
    (comp (ref "R37")
      (value "Res3")
      (footprint "RES_0805")
      (description "Resistor")
      (fields (field (name "ALTIUM_VALUE") "22.1") (field (name "PUBLISHER") "Altium Limited"))
      (libsource (lib "Miscellaneous Devices") (part "Res3"))
    )
    (comp (ref "R38")
      (value "Res3")
      (footprint "RES_1206")
      (description "Resistor")
      (fields (field (name "ALTIUM_VALUE") "270") (field (name "PUBLISHER") "Altium Limited"))
      (libsource (lib "Miscellaneous Devices") (part "Res3"))
    )
    (comp (ref "R39")
      (value "Res3")
      (footprint "RES_1206")
      (description "Resistor")
      (fields (field (name "ALTIUM_VALUE") "270") (field (name "PUBLISHER") "Altium Limited"))
      (libsource (lib "Miscellaneous Devices") (part "Res3"))
    )
    (comp (ref "R40")
      (value "Res3")
      (footprint "RES_1206")
      (description "Resistor")
      (fields (field (name "ALTIUM_VALUE") "270") (field (name "PUBLISHER") "Altium Limited"))
      (libsource (lib "Miscellaneous Devices") (part "Res3"))
    )
    (comp (ref "R41")
      (value "Res3")
      (footprint "J1-0603")
      (description "Resistor")
      (fields (field (name "ALTIUM_VALUE") "2.21") (field (name "PUBLISHER") "Altium Limited"))
      (libsource (lib "Miscellaneous Devices") (part "Res3"))
    )
    (comp (ref "R42")
      (value "Res3")
      (footprint "RES_1206")
      (description "Resistor")
      (fields (field (name "ALTIUM_VALUE") "270") (field (name "PUBLISHER") "Altium Limited"))
      (libsource (lib "Miscellaneous Devices") (part "Res3"))
    )
    (comp (ref "R43")
      (value "Res3")
      (footprint "J1-0603")
      (description "Resistor")
      (fields (field (name "ALTIUM_VALUE") "2.21") (field (name "PUBLISHER") "Altium Limited"))
      (libsource (lib "Miscellaneous Devices") (part "Res3"))
    )
    (comp (ref "R44")
      (value "Res3")
      (footprint "RES_1206")
      (description "Resistor")
      (fields (field (name "ALTIUM_VALUE") "270") (field (name "PUBLISHER") "Altium Limited"))
      (libsource (lib "Miscellaneous Devices") (part "Res3"))
    )
    (comp (ref "R45")
      (value "Res3")
      (footprint "RES_1206")
      (description "Resistor")
      (fields (field (name "ALTIUM_VALUE") "270") (field (name "PUBLISHER") "Altium Limited"))
      (libsource (lib "Miscellaneous Devices") (part "Res3"))
    )
    (comp (ref "R46")
      (value "Res3")
      (footprint "RES_1206")
      (description "Resistor")
      (fields (field (name "ALTIUM_VALUE") "270") (field (name "PUBLISHER") "Altium Limited"))
      (libsource (lib "Miscellaneous Devices") (part "Res3"))
    )
    (comp (ref "R47")
      (value "Res3")
      (footprint "J1-0603")
      (description "Resistor")
      (fields (field (name "ALTIUM_VALUE") "2.21") (field (name "PUBLISHER") "Altium Limited"))
      (libsource (lib "Miscellaneous Devices") (part "Res3"))
    )
    (comp (ref "R48")
      (value "Res3")
      (footprint "RES_1206")
      (description "Resistor")
      (fields (field (name "ALTIUM_VALUE") "270") (field (name "PUBLISHER") "Altium Limited"))
      (libsource (lib "Miscellaneous Devices") (part "Res3"))
    )
    (comp (ref "R49")
      (value "Res3")
      (footprint "J1-0603")
      (description "Resistor")
      (fields (field (name "ALTIUM_VALUE") "2.21") (field (name "PUBLISHER") "Altium Limited"))
      (libsource (lib "Miscellaneous Devices") (part "Res3"))
    )
    (comp (ref "R50")
      (value "Res3")
      (footprint "RES_1206")
      (description "Resistor")
      (fields (field (name "ALTIUM_VALUE") "270") (field (name "PUBLISHER") "Altium Limited"))
      (libsource (lib "Miscellaneous Devices") (part "Res3"))
    )
    (comp (ref "R51")
      (value "Res3")
      (footprint "RES_1206")
      (description "Resistor")
      (fields (field (name "ALTIUM_VALUE") "270") (field (name "PUBLISHER") "Altium Limited"))
      (libsource (lib "Miscellaneous Devices") (part "Res3"))
    )
    (comp (ref "R52")
      (value "Res3")
      (footprint "RES_1206")
      (description "Resistor")
      (fields (field (name "ALTIUM_VALUE") "270") (field (name "PUBLISHER") "Altium Limited"))
      (libsource (lib "Miscellaneous Devices") (part "Res3"))
    )
    (comp (ref "R53")
      (value "Res3")
      (footprint "J1-0603")
      (description "Resistor")
      (fields (field (name "ALTIUM_VALUE") "2.21") (field (name "PUBLISHER") "Altium Limited"))
      (libsource (lib "Miscellaneous Devices") (part "Res3"))
    )
    (comp (ref "R54")
      (value "Res3")
      (footprint "RES_1206")
      (description "Resistor")
      (fields (field (name "ALTIUM_VALUE") "270") (field (name "PUBLISHER") "Altium Limited"))
      (libsource (lib "Miscellaneous Devices") (part "Res3"))
    )
    (comp (ref "R55")
      (value "Res3")
      (footprint "J1-0603")
      (description "Resistor")
      (fields (field (name "ALTIUM_VALUE") "2.21") (field (name "PUBLISHER") "Altium Limited"))
      (libsource (lib "Miscellaneous Devices") (part "Res3"))
    )
    (comp (ref "R56")
      (value "Res3")
      (footprint "RES_1206")
      (description "Resistor")
      (fields (field (name "ALTIUM_VALUE") "270") (field (name "PUBLISHER") "Altium Limited"))
      (libsource (lib "Miscellaneous Devices") (part "Res3"))
    )
    (comp (ref "R57")
      (value "Res3")
      (footprint "RES_1206")
      (description "Resistor")
      (fields (field (name "ALTIUM_VALUE") "270") (field (name "PUBLISHER") "Altium Limited"))
      (libsource (lib "Miscellaneous Devices") (part "Res3"))
    )
    (comp (ref "R58")
      (value "Res3")
      (footprint "RES_1206")
      (description "Resistor")
      (fields (field (name "ALTIUM_VALUE") "270") (field (name "PUBLISHER") "Altium Limited"))
      (libsource (lib "Miscellaneous Devices") (part "Res3"))
    )
    (comp (ref "R59")
      (value "Res3")
      (footprint "J1-0603")
      (description "Resistor")
      (fields (field (name "ALTIUM_VALUE") "2.21") (field (name "PUBLISHER") "Altium Limited"))
      (libsource (lib "Miscellaneous Devices") (part "Res3"))
    )
    (comp (ref "R60")
      (value "Res3")
      (footprint "RES_1206")
      (description "Resistor")
      (fields (field (name "ALTIUM_VALUE") "270") (field (name "PUBLISHER") "Altium Limited"))
      (libsource (lib "Miscellaneous Devices") (part "Res3"))
    )
    (comp (ref "R61")
      (value "Res3")
      (footprint "J1-0603")
      (description "Resistor")
      (fields (field (name "ALTIUM_VALUE") "2.21") (field (name "PUBLISHER") "Altium Limited"))
      (libsource (lib "Miscellaneous Devices") (part "Res3"))
    )
    (comp (ref "R62")
      (value "Res3")
      (footprint "RES_1206")
      (description "Resistor")
      (fields
        (field (name "ALTIUM_VALUE") "18.7K")
        (field (name "TOL") "1%")
        (field (name "PUBLISHER") "Altium Limited")
      )
      (libsource (lib "Miscellaneous Devices") (part "Res3"))
    )
    (comp (ref "R63")
      (value "Res3")
      (footprint "RES_2010")
      (description "Resistor")
      (fields (field (name "ALTIUM_VALUE") "100") (field (name "PUBLISHER") "Altium Limited"))
      (libsource (lib "Miscellaneous Devices") (part "Res3"))
    )
    (comp (ref "R64")
      (value "Res3")
      (footprint "RES_1206")
      (description "Resistor")
      (fields (field (name "ALTIUM_VALUE") "62") (field (name "PUBLISHER") "Altium Limited"))
      (libsource (lib "Miscellaneous Devices") (part "Res3"))
    )
    (comp (ref "R65")
      (value "Res3")
      (footprint "RES_0805")
      (description "Resistor")
      (fields (field (name "ALTIUM_VALUE") "47") (field (name "PUBLISHER") "Altium Limited"))
      (libsource (lib "Miscellaneous Devices") (part "Res3"))
    )
    (comp (ref "R66")
      (value "Res3")
      (footprint "J1-0603")
      (description "Resistor")
      (fields (field (name "ALTIUM_VALUE") "24") (field (name "PUBLISHER") "Altium Limited"))
      (libsource (lib "Miscellaneous Devices") (part "Res3"))
    )
    (comp (ref "R67")
      (value "Res3")
      (footprint "RES_1206")
      (description "Resistor")
      (fields
        (field (name "ALTIUM_VALUE") "18.7K")
        (field (name "TOL") "1%")
        (field (name "PUBLISHER") "Altium Limited")
      )
      (libsource (lib "Miscellaneous Devices") (part "Res3"))
    )
    (comp (ref "R68")
      (value "Res3")
      (footprint "RES_2010")
      (description "Resistor")
      (fields (field (name "ALTIUM_VALUE") "100") (field (name "PUBLISHER") "Altium Limited"))
      (libsource (lib "Miscellaneous Devices") (part "Res3"))
    )
    (comp (ref "R69")
      (value "Res3")
      (footprint "RES_1206")
      (description "Resistor")
      (fields (field (name "ALTIUM_VALUE") "62") (field (name "PUBLISHER") "Altium Limited"))
      (libsource (lib "Miscellaneous Devices") (part "Res3"))
    )
    (comp (ref "R70")
      (value "Res3")
      (footprint "RES_0805")
      (description "Resistor")
      (fields (field (name "ALTIUM_VALUE") "47") (field (name "PUBLISHER") "Altium Limited"))
      (libsource (lib "Miscellaneous Devices") (part "Res3"))
    )
    (comp (ref "R71")
      (value "Res3")
      (footprint "J1-0603")
      (description "Resistor")
      (fields (field (name "ALTIUM_VALUE") "24") (field (name "PUBLISHER") "Altium Limited"))
      (libsource (lib "Miscellaneous Devices") (part "Res3"))
    )
    (comp (ref "R72")
      (value "Res3")
      (footprint "RES_1206")
      (description "Resistor")
      (fields
        (field (name "ALTIUM_VALUE") "18.7K")
        (field (name "TOL") "1%")
        (field (name "PUBLISHER") "Altium Limited")
      )
      (libsource (lib "Miscellaneous Devices") (part "Res3"))
    )
    (comp (ref "R73")
      (value "Res3")
      (footprint "RES_2010")
      (description "Resistor")
      (fields (field (name "ALTIUM_VALUE") "100") (field (name "PUBLISHER") "Altium Limited"))
      (libsource (lib "Miscellaneous Devices") (part "Res3"))
    )
    (comp (ref "R74")
      (value "Res3")
      (footprint "RES_1206")
      (description "Resistor")
      (fields (field (name "ALTIUM_VALUE") "62") (field (name "PUBLISHER") "Altium Limited"))
      (libsource (lib "Miscellaneous Devices") (part "Res3"))
    )
    (comp (ref "R75")
      (value "Res3")
      (footprint "RES_0805")
      (description "Resistor")
      (fields (field (name "ALTIUM_VALUE") "47") (field (name "PUBLISHER") "Altium Limited"))
      (libsource (lib "Miscellaneous Devices") (part "Res3"))
    )
    (comp (ref "R76")
      (value "Res3")
      (footprint "J1-0603")
      (description "Resistor")
      (fields (field (name "ALTIUM_VALUE") "24") (field (name "PUBLISHER") "Altium Limited"))
      (libsource (lib "Miscellaneous Devices") (part "Res3"))
    )
    (comp (ref "R77")
      (value "Res3")
      (footprint "RES_1206")
      (description "Resistor")
      (fields
        (field (name "ALTIUM_VALUE") "18.7K")
        (field (name "TOL") "1%")
        (field (name "PUBLISHER") "Altium Limited")
      )
      (libsource (lib "Miscellaneous Devices") (part "Res3"))
    )
    (comp (ref "R78")
      (value "Res3")
      (footprint "RES_2010")
      (description "Resistor")
      (fields (field (name "ALTIUM_VALUE") "100") (field (name "PUBLISHER") "Altium Limited"))
      (libsource (lib "Miscellaneous Devices") (part "Res3"))
    )
    (comp (ref "R79")
      (value "Res3")
      (footprint "RES_1206")
      (description "Resistor")
      (fields (field (name "ALTIUM_VALUE") "62") (field (name "PUBLISHER") "Altium Limited"))
      (libsource (lib "Miscellaneous Devices") (part "Res3"))
    )
    (comp (ref "R80")
      (value "Res3")
      (footprint "RES_0805")
      (description "Resistor")
      (fields (field (name "ALTIUM_VALUE") "47") (field (name "PUBLISHER") "Altium Limited"))
      (libsource (lib "Miscellaneous Devices") (part "Res3"))
    )
    (comp (ref "R81")
      (value "Res3")
      (footprint "J1-0603")
      (description "Resistor")
      (fields (field (name "ALTIUM_VALUE") "24") (field (name "PUBLISHER") "Altium Limited"))
      (libsource (lib "Miscellaneous Devices") (part "Res3"))
    )
    (comp (ref "R82")
      (value "Res3")
      (footprint "RES_2010")
      (description "Resistor")
      (fields (field (name "ALTIUM_VALUE") "100") (field (name "PUBLISHER") "Altium Limited"))
      (libsource (lib "Miscellaneous Devices") (part "Res3"))
    )
    (comp (ref "R83")
      (value "Res3")
      (footprint "RES_1206")
      (description "Resistor")
      (fields (field (name "ALTIUM_VALUE") "62") (field (name "PUBLISHER") "Altium Limited"))
      (libsource (lib "Miscellaneous Devices") (part "Res3"))
    )
    (comp (ref "R84")
      (value "Res3")
      (footprint "RES_0805")
      (description "Resistor")
      (fields (field (name "ALTIUM_VALUE") "47") (field (name "PUBLISHER") "Altium Limited"))
      (libsource (lib "Miscellaneous Devices") (part "Res3"))
    )
    (comp (ref "R85")
      (value "Res3")
      (footprint "J1-0603")
      (description "Resistor")
      (fields (field (name "ALTIUM_VALUE") "24") (field (name "PUBLISHER") "Altium Limited"))
      (libsource (lib "Miscellaneous Devices") (part "Res3"))
    )
    (comp (ref "R86")
      (value "Res3")
      (footprint "RES_2010")
      (description "Resistor")
      (fields (field (name "ALTIUM_VALUE") "100") (field (name "PUBLISHER") "Altium Limited"))
      (libsource (lib "Miscellaneous Devices") (part "Res3"))
    )
    (comp (ref "R87")
      (value "Res3")
      (footprint "RES_1206")
      (description "Resistor")
      (fields (field (name "ALTIUM_VALUE") "62") (field (name "PUBLISHER") "Altium Limited"))
      (libsource (lib "Miscellaneous Devices") (part "Res3"))
    )
    (comp (ref "R88")
      (value "Res3")
      (footprint "RES_0805")
      (description "Resistor")
      (fields (field (name "ALTIUM_VALUE") "47") (field (name "PUBLISHER") "Altium Limited"))
      (libsource (lib "Miscellaneous Devices") (part "Res3"))
    )
    (comp (ref "R89")
      (value "Res3")
      (footprint "J1-0603")
      (description "Resistor")
      (fields (field (name "ALTIUM_VALUE") "24") (field (name "PUBLISHER") "Altium Limited"))
      (libsource (lib "Miscellaneous Devices") (part "Res3"))
    )
    (comp (ref "R90")
      (value "Res3")
      (footprint "RES_2010")
      (description "Resistor")
      (fields (field (name "ALTIUM_VALUE") "100") (field (name "PUBLISHER") "Altium Limited"))
      (libsource (lib "Miscellaneous Devices") (part "Res3"))
    )
    (comp (ref "R91")
      (value "Res3")
      (footprint "RES_1206")
      (description "Resistor")
      (fields (field (name "ALTIUM_VALUE") "62") (field (name "PUBLISHER") "Altium Limited"))
      (libsource (lib "Miscellaneous Devices") (part "Res3"))
    )
    (comp (ref "R92")
      (value "Res3")
      (footprint "RES_0805")
      (description "Resistor")
      (fields (field (name "ALTIUM_VALUE") "47") (field (name "PUBLISHER") "Altium Limited"))
      (libsource (lib "Miscellaneous Devices") (part "Res3"))
    )
    (comp (ref "R93")
      (value "Res3")
      (footprint "J1-0603")
      (description "Resistor")
      (fields (field (name "ALTIUM_VALUE") "24") (field (name "PUBLISHER") "Altium Limited"))
      (libsource (lib "Miscellaneous Devices") (part "Res3"))
    )
    (comp (ref "R94")
      (value "Res3")
      (footprint "RES_2010")
      (description "Resistor")
      (fields (field (name "ALTIUM_VALUE") "100") (field (name "PUBLISHER") "Altium Limited"))
      (libsource (lib "Miscellaneous Devices") (part "Res3"))
    )
    (comp (ref "R95")
      (value "Res3")
      (footprint "RES_1206")
      (description "Resistor")
      (fields (field (name "ALTIUM_VALUE") "62") (field (name "PUBLISHER") "Altium Limited"))
      (libsource (lib "Miscellaneous Devices") (part "Res3"))
    )
    (comp (ref "R96")
      (value "Res3")
      (footprint "RES_0805")
      (description "Resistor")
      (fields (field (name "ALTIUM_VALUE") "47") (field (name "PUBLISHER") "Altium Limited"))
      (libsource (lib "Miscellaneous Devices") (part "Res3"))
    )
    (comp (ref "R97")
      (value "Res3")
      (footprint "J1-0603")
      (description "Resistor")
      (fields (field (name "ALTIUM_VALUE") "24") (field (name "PUBLISHER") "Altium Limited"))
      (libsource (lib "Miscellaneous Devices") (part "Res3"))
    )
    (comp (ref "R230")
      (value "430")
      (footprint "J1-0603")
      (description "Resistor")
      (fields (field (name "Comment") "Res3") (field (name "PUBLISHER") "Altium Limited"))
      (libsource (lib "Miscellaneous Devices") (part "Res3"))
    )
    (comp (ref "R235")
      (value "430")
      (footprint "J1-0603")
      (description "Resistor")
      (fields (field (name "Comment") "Res3") (field (name "PUBLISHER") "Altium Limited"))
      (libsource (lib "Miscellaneous Devices") (part "Res3"))
    )
    (comp (ref "R240")
      (value "430")
      (footprint "J1-0603")
      (description "Resistor")
      (fields (field (name "Comment") "Res3") (field (name "PUBLISHER") "Altium Limited"))
      (libsource (lib "Miscellaneous Devices") (part "Res3"))
    )
    (comp (ref "R245")
      (value "430")
      (footprint "J1-0603")
      (description "Resistor")
      (fields (field (name "Comment") "Res3") (field (name "PUBLISHER") "Altium Limited"))
      (libsource (lib "Miscellaneous Devices") (part "Res3"))
    )
    (comp (ref "R250")
      (value "10k")
      (footprint "J1-0603")
      (description "Resistor")
      (fields (field (name "Comment") "Res3") (field (name "PUBLISHER") "Altium Limited"))
      (libsource (lib "Miscellaneous Devices") (part "Res3"))
    )
    (comp (ref "R256")
      (value "10k")
      (footprint "J1-0603")
      (description "Resistor")
      (fields (field (name "Comment") "Res3") (field (name "PUBLISHER") "Altium Limited"))
      (libsource (lib "Miscellaneous Devices") (part "Res3"))
    )
    (comp (ref "R261")
      (value "10k")
      (footprint "J1-0603")
      (description "Resistor")
      (fields (field (name "Comment") "Res3") (field (name "PUBLISHER") "Altium Limited"))
      (libsource (lib "Miscellaneous Devices") (part "Res3"))
    )
    (comp (ref "R265")
      (value "10k")
      (footprint "J1-0603")
      (description "Resistor")
      (fields (field (name "Comment") "Res3") (field (name "PUBLISHER") "Altium Limited"))
      (libsource (lib "Miscellaneous Devices") (part "Res3"))
    )
    (comp (ref "R269")
      (value "430")
      (footprint "J1-0603")
      (description "Resistor")
      (fields (field (name "Comment") "Res3") (field (name "PUBLISHER") "Altium Limited"))
      (libsource (lib "Miscellaneous Devices") (part "Res3"))
    )
    (comp (ref "R369")
      (value "430")
      (footprint "J1-0603")
      (description "Resistor")
      (fields (field (name "Comment") "Res3") (field (name "PUBLISHER") "Altium Limited"))
      (libsource (lib "Miscellaneous Devices") (part "Res3"))
    )
    (comp (ref "R371")
      (value "430")
      (footprint "J1-0603")
      (description "Resistor")
      (fields (field (name "Comment") "Res3") (field (name "PUBLISHER") "Altium Limited"))
      (libsource (lib "Miscellaneous Devices") (part "Res3"))
    )
    (comp (ref "R373")
      (value "430")
      (footprint "J1-0603")
      (description "Resistor")
      (fields (field (name "Comment") "Res3") (field (name "PUBLISHER") "Altium Limited"))
      (libsource (lib "Miscellaneous Devices") (part "Res3"))
    )
    (comp (ref "REG1")
      (value "TPS73801_DCQ6")
      (footprint "TPS73801_DCQ6")
      (fields (field (name "SUPPLIER PART NUMBER 1") "296-39489-1-ND"))
      (libsource (lib "Lib1") (part "TPS73801_DCQ6"))
    )
    (comp (ref "REG2")
      (value "TPS73801_DCQ6")
      (footprint "TPS73801_DCQ6")
      (fields (field (name "SUPPLIER PART NUMBER 1") "296-39489-1-ND"))
      (libsource (lib "Lib1") (part "TPS73801_DCQ6"))
    )
    (comp (ref "REG3")
      (value "TPS73801_DCQ6")
      (footprint "TPS73801_DCQ6")
      (fields (field (name "SUPPLIER PART NUMBER 1") "296-39489-1-ND"))
      (libsource (lib "Lib1") (part "TPS73801_DCQ6"))
    )
    (comp (ref "REG4")
      (value "TPS73801_DCQ6")
      (footprint "TPS73801_DCQ6")
      (fields (field (name "SUPPLIER PART NUMBER 1") "296-39489-1-ND"))
      (libsource (lib "Lib1") (part "TPS73801_DCQ6"))
    )
    (comp (ref "REG5")
      (value "TPS73801_DCQ6")
      (footprint "TPS73801_DCQ6")
      (fields (field (name "SUPPLIER PART NUMBER 1") "296-39489-1-ND"))
      (libsource (lib "Lib1") (part "TPS73801_DCQ6"))
    )
    (comp (ref "RPOT1")
      (value "TS63Y_POT")
      (footprint "TS63Y_POT")
      (fields (field (name "SUPPLIER PART NUMBER 1") "TS63Y-200CT-ND"))
      (libsource (lib "Lib1") (part "TS63Y_POT"))
    )
    (comp (ref "RPOT2")
      (value "TS63Y_POT")
      (footprint "TS63Y_POT")
      (fields (field (name "SUPPLIER PART NUMBER 1") "TS63Y-200CT-ND"))
      (libsource (lib "Lib1") (part "TS63Y_POT"))
    )
    (comp (ref "RPOT3")
      (value "TS63Y_POT")
      (footprint "TS63Y_POT")
      (fields (field (name "SUPPLIER PART NUMBER 1") "TS63Y-200CT-ND"))
      (libsource (lib "Lib1") (part "TS63Y_POT"))
    )
    (comp (ref "RPOT4")
      (value "TS63Y_POT")
      (footprint "TS63Y_POT")
      (fields (field (name "SUPPLIER PART NUMBER 1") "TS63Y-200CT-ND"))
      (libsource (lib "Lib1") (part "TS63Y_POT"))
    )
    (comp (ref "RPOT5")
      (value "TS63Y_POT")
      (footprint "TS63Y_POT")
      (fields (field (name "SUPPLIER PART NUMBER 1") "TS63Y-200CT-ND"))
      (libsource (lib "Lib1") (part "TS63Y_POT"))
    )
    (comp (ref "TP18")
      (value "Test Point")
      (footprint "TestPoint")
      (libsource (lib "Lib1") (part "Test Point"))
    )
    (comp (ref "TP20")
      (value "Test Point")
      (footprint "TestPoint")
      (libsource (lib "Lib1") (part "Test Point"))
    )
    (comp (ref "U1")
      (value "OPA564_HSOP20_BOTTOM")
      (footprint "OPA564_HSOP20_BOTTOM")
      (fields (field (name "SUPPLIER PART NUMBER 1") "296-25592-5-ND"))
      (libsource (lib "Lib1") (part "OPA564_HSOP20_BOTTOM"))
    )
    (comp (ref "U2")
      (value "OPA564_HSOP20_BOTTOM")
      (footprint "OPA564_HSOP20_BOTTOM")
      (fields (field (name "SUPPLIER PART NUMBER 1") "296-25592-5-ND"))
      (libsource (lib "Lib1") (part "OPA564_HSOP20_BOTTOM"))
    )
    (comp (ref "U3")
      (value "OPA564_HSOP20_BOTTOM")
      (footprint "OPA564_HSOP20_BOTTOM")
      (fields (field (name "SUPPLIER PART NUMBER 1") "296-25592-5-ND"))
      (libsource (lib "Lib1") (part "OPA564_HSOP20_BOTTOM"))
    )
    (comp (ref "U4")
      (value "OPA564_HSOP20_BOTTOM")
      (footprint "OPA564_HSOP20_BOTTOM")
      (fields (field (name "SUPPLIER PART NUMBER 1") "296-25592-5-ND"))
      (libsource (lib "Lib1") (part "OPA564_HSOP20_BOTTOM"))
    )
    (comp (ref "U5")
      (value "THS4226_10SOP")
      (footprint "THS4226_10SOP")
      (fields (field (name "SUPPLIER PART NUMBER 1") "296-13639-5-ND"))
      (libsource (lib "Lib1") (part "THS4226_10SOP"))
    )
    (comp (ref "U6")
      (value "THS4226_10SOP")
      (footprint "THS4226_10SOP")
      (fields (field (name "SUPPLIER PART NUMBER 1") "296-13639-5-ND"))
      (libsource (lib "Lib1") (part "THS4226_10SOP"))
    )
    (comp (ref "U33")
      (value "SN74LV244A_TSOP20")
      (footprint "SN74LV244A_TSOP20")
      (fields (field (name "SUPPLIER PART NUMBER 1") "296-27806-1-ND"))
      (libsource (lib "Lib1") (part "SN74LV244A_TSOP20"))
    )
  )
  (nets
    (net (code "1") (name "/15V") (class "Default")
      (node (ref "C1") (pin "2") (pinfunction "2_2") (pintype "passive"))
      (node (ref "C10") (pin "2") (pinfunction "2_2") (pintype "passive"))
      (node (ref "C11") (pin "2") (pinfunction "2_2") (pintype "passive"))
      (node (ref "C13") (pin "2") (pinfunction "2_2") (pintype "passive"))
      (node (ref "C14") (pin "2") (pinfunction "2_2") (pintype "passive"))
      (node (ref "C2") (pin "2") (pinfunction "2_2") (pintype "passive"))
      (node (ref "C4") (pin "2") (pinfunction "2_2") (pintype "passive"))
      (node (ref "C5") (pin "2") (pinfunction "2_2") (pintype "passive"))
      (node (ref "C7") (pin "2") (pinfunction "2_2") (pintype "passive"))
      (node (ref "C8") (pin "2") (pinfunction "2_2") (pintype "passive"))
      (node (ref "REG1") (pin "1") (pinfunction "IN_1") (pintype "passive"))
      (node (ref "REG2") (pin "1") (pinfunction "IN_1") (pintype "passive"))
      (node (ref "REG3") (pin "1") (pinfunction "IN_1") (pintype "passive"))
      (node (ref "REG4") (pin "1") (pinfunction "IN_1") (pintype "passive"))
      (node (ref "REG5") (pin "1") (pinfunction "IN_1") (pintype "passive"))
    )
    (net (code "2") (name "/A1V") (class "Default")
      (node (ref "C44") (pin "2") (pinfunction "2_2") (pintype "passive"))
      (node (ref "C45") (pin "2") (pinfunction "2_2") (pintype "passive"))
      (node (ref "C48") (pin "2") (pinfunction "2_2") (pintype "passive"))
      (node (ref "C49") (pin "2") (pinfunction "2_2") (pintype "passive"))
      (node (ref "P4") (pin "1") (pinfunction "1_1") (pintype "passive"))
    )
    (net (code "3") (name "/A3V3") (class "Default")
      (node (ref "C16") (pin "2") (pinfunction "2_2") (pintype "passive"))
      (node (ref "C17") (pin "2") (pinfunction "2_2") (pintype "passive"))
      (node (ref "C18") (pin "2") (pinfunction "2_2") (pintype "passive"))
      (node (ref "C19") (pin "2") (pinfunction "2_2") (pintype "passive"))
      (node (ref "C20") (pin "2") (pinfunction "2_2") (pintype "passive"))
      (node (ref "C21") (pin "2") (pinfunction "2_2") (pintype "passive"))
      (node (ref "DPOT1") (pin "5") (pinfunction "VDD_5") (pintype "passive"))
      (node (ref "DPOT2") (pin "5") (pinfunction "VDD_5") (pintype "passive"))
      (node (ref "DPOT3") (pin "5") (pinfunction "VDD_5") (pintype "passive"))
      (node (ref "R230") (pin "1") (pinfunction "1_1") (pintype "passive"))
      (node (ref "R235") (pin "1") (pinfunction "1_1") (pintype "passive"))
      (node (ref "R240") (pin "1") (pinfunction "1_1") (pintype "passive"))
      (node (ref "R245") (pin "1") (pinfunction "1_1") (pintype "passive"))
      (node (ref "R269") (pin "1") (pinfunction "1_1") (pintype "passive"))
      (node (ref "R369") (pin "1") (pinfunction "1_1") (pintype "passive"))
      (node (ref "R371") (pin "1") (pinfunction "1_1") (pintype "passive"))
      (node (ref "R373") (pin "1") (pinfunction "1_1") (pintype "passive"))
    )
    (net (code "4") (name "/D3V3") (class "Default")
      (node (ref "C152") (pin "2") (pinfunction "2_2") (pintype "passive"))
      (node (ref "U33") (pin "20") (pinfunction "VCC_20") (pintype "passive"))
    )
    (net (code "5") (name "/EN1") (class "Default")
      (node (ref "U33") (pin "2") (pinfunction "1A1_2") (pintype "passive"))
    )
    (net (code "6") (name "/EN2") (class "Default")
      (node (ref "U33") (pin "4") (pinfunction "1A2_4") (pintype "passive"))
    )
    (net (code "7") (name "/EN3") (class "Default")
      (node (ref "U33") (pin "6") (pinfunction "1A3_6") (pintype "passive"))
    )
    (net (code "8") (name "/EN4") (class "Default")
      (node (ref "U33") (pin "8") (pinfunction "1A4_8") (pintype "passive"))
    )
    (net (code "9") (name "/EN5") (class "Default")
      (node (ref "U33") (pin "11") (pinfunction "2A1_11") (pintype "passive"))
    )
    (net (code "10") (name "/EN6") (class "Default")
      (node (ref "U33") (pin "13") (pinfunction "2A2_13") (pintype "passive"))
    )
    (net (code "11") (name "/EN7") (class "Default")
      (node (ref "U33") (pin "15") (pinfunction "2A3_15") (pintype "passive"))
    )
    (net (code "12") (name "/EN8") (class "Default")
      (node (ref "U33") (pin "17") (pinfunction "2A4_17") (pintype "passive"))
    )
    (net (code "13") (name "/EN9") (class "Default")
      (node (ref "REG1") (pin "5") (pinfunction "EN_5") (pintype "passive"))
    )
    (net (code "14") (name "/EN10") (class "Default")
      (node (ref "REG2") (pin "5") (pinfunction "EN_5") (pintype "passive"))
    )
    (net (code "15") (name "/EN11") (class "Default")
      (node (ref "REG3") (pin "5") (pinfunction "EN_5") (pintype "passive"))
    )
    (net (code "16") (name "/EN12") (class "Default")
      (node (ref "REG4") (pin "5") (pinfunction "EN_5") (pintype "passive"))
    )
    (net (code "17") (name "/EN13") (class "Default")
      (node (ref "REG5") (pin "5") (pinfunction "EN_5") (pintype "passive"))
    )
    (net (code "18") (name "/ENE1") (class "Default")
      (node (ref "OPT2") (pin "5") (pinfunction "COLL_5") (pintype "passive"))
      (node (ref "U1") (pin "4") (pinfunction "E/~{S}_4") (pintype "passive"))
    )
    (net (code "19") (name "/ENE2") (class "Default")
      (node (ref "OPT1") (pin "5") (pinfunction "COLL_5") (pintype "passive"))
      (node (ref "U2") (pin "4") (pinfunction "E/~{S}_4") (pintype "passive"))
    )
    (net (code "20") (name "/ENE3") (class "Default")
      (node (ref "OPT4") (pin "5") (pinfunction "COLL_5") (pintype "passive"))
      (node (ref "U3") (pin "4") (pinfunction "E/~{S}_4") (pintype "passive"))
    )
    (net (code "21") (name "/ENE4") (class "Default")
      (node (ref "OPT3") (pin "5") (pinfunction "COLL_5") (pintype "passive"))
      (node (ref "U4") (pin "4") (pinfunction "E/~{S}_4") (pintype "passive"))
    )
    (net (code "22") (name "/ENE5") (class "Default")
      (node (ref "OPT5") (pin "5") (pinfunction "COLL_5") (pintype "passive"))
      (node (ref "U5") (pin "5") (pinfunction "~{1PD}_5") (pintype "passive"))
    )
    (net (code "23") (name "/ENE6") (class "Default")
      (node (ref "OPT6") (pin "5") (pinfunction "COLL_5") (pintype "passive"))
      (node (ref "U5") (pin "6") (pinfunction "~{2PD}_6") (pintype "passive"))
    )
    (net (code "24") (name "/ENE7") (class "Default")
      (node (ref "OPT7") (pin "5") (pinfunction "COLL_5") (pintype "passive"))
      (node (ref "U6") (pin "5") (pinfunction "~{1PD}_5") (pintype "passive"))
    )
    (net (code "25") (name "/ENE8") (class "Default")
      (node (ref "OPT8") (pin "5") (pinfunction "COLL_5") (pintype "passive"))
      (node (ref "U6") (pin "6") (pinfunction "~{2PD}_6") (pintype "passive"))
    )
    (net (code "26") (name "/ENO1") (class "Default")
      (node (ref "OPT2") (pin "2") (pinfunction "CAT_2") (pintype "passive"))
      (node (ref "U33") (pin "18") (pinfunction "1Y1_18") (pintype "passive"))
    )
    (net (code "27") (name "/ENO2") (class "Default")
      (node (ref "OPT1") (pin "2") (pinfunction "CAT_2") (pintype "passive"))
      (node (ref "U33") (pin "16") (pinfunction "1Y2_16") (pintype "passive"))
    )
    (net (code "28") (name "/ENO3") (class "Default")
      (node (ref "OPT4") (pin "2") (pinfunction "CAT_2") (pintype "passive"))
      (node (ref "U33") (pin "14") (pinfunction "1Y3_14") (pintype "passive"))
    )
    (net (code "29") (name "/ENO4") (class "Default")
      (node (ref "OPT3") (pin "2") (pinfunction "CAT_2") (pintype "passive"))
      (node (ref "U33") (pin "12") (pinfunction "1Y4_12") (pintype "passive"))
    )
    (net (code "30") (name "/ENO5") (class "Default")
      (node (ref "OPT5") (pin "2") (pinfunction "CAT_2") (pintype "passive"))
      (node (ref "U33") (pin "9") (pinfunction "2Y1_9") (pintype "passive"))
    )
    (net (code "31") (name "/ENO6") (class "Default")
      (node (ref "OPT6") (pin "2") (pinfunction "CAT_2") (pintype "passive"))
      (node (ref "U33") (pin "7") (pinfunction "2Y2_7") (pintype "passive"))
    )
    (net (code "32") (name "/ENO7") (class "Default")
      (node (ref "OPT7") (pin "2") (pinfunction "CAT_2") (pintype "passive"))
      (node (ref "U33") (pin "5") (pinfunction "2Y3_5") (pintype "passive"))
    )
    (net (code "33") (name "/ENO8") (class "Default")
      (node (ref "OPT8") (pin "2") (pinfunction "CAT_2") (pintype "passive"))
      (node (ref "U33") (pin "3") (pinfunction "2Y4_3") (pintype "passive"))
    )
    (net (code "35") (name "/FB1") (class "Default")
      (node (ref "DPOT1") (pin "10") (pinfunction "W1_10") (pintype "passive"))
      (node (ref "REG1") (pin "4") (pinfunction "FB_4") (pintype "passive"))
      (node (ref "RPOT1") (pin "1") (pinfunction "a_1") (pintype "passive"))
    )
    (net (code "36") (name "/FB2") (class "Default")
      (node (ref "DPOT1") (pin "3") (pinfunction "W2_3") (pintype "passive"))
      (node (ref "REG2") (pin "4") (pinfunction "FB_4") (pintype "passive"))
      (node (ref "RPOT2") (pin "1") (pinfunction "a_1") (pintype "passive"))
    )
    (net (code "37") (name "/FB3") (class "Default")
      (node (ref "DPOT2") (pin "10") (pinfunction "W1_10") (pintype "passive"))
      (node (ref "REG3") (pin "4") (pinfunction "FB_4") (pintype "passive"))
      (node (ref "RPOT3") (pin "1") (pinfunction "a_1") (pintype "passive"))
    )
    (net (code "38") (name "/FB4") (class "Default")
      (node (ref "DPOT2") (pin "3") (pinfunction "W2_3") (pintype "passive"))
      (node (ref "REG4") (pin "4") (pinfunction "FB_4") (pintype "passive"))
      (node (ref "RPOT4") (pin "1") (pinfunction "a_1") (pintype "passive"))
    )
    (net (code "39") (name "/FBR") (class "Default")
      (node (ref "DPOT3") (pin "10") (pinfunction "W1_10") (pintype "passive"))
      (node (ref "REG5") (pin "4") (pinfunction "FB_4") (pintype "passive"))
      (node (ref "RPOT5") (pin "1") (pinfunction "a_1") (pintype "passive"))
    )
    (net (code "40") (name "/GND") (class "Default")
      (node (ref "C1") (pin "1") (pinfunction "1_1") (pintype "passive"))
      (node (ref "C10") (pin "1") (pinfunction "1_1") (pintype "passive"))
      (node (ref "C11") (pin "1") (pinfunction "1_1") (pintype "passive"))
      (node (ref "C12") (pin "1") (pinfunction "1_1") (pintype "passive"))
      (node (ref "C13") (pin "1") (pinfunction "1_1") (pintype "passive"))
      (node (ref "C14") (pin "1") (pinfunction "1_1") (pintype "passive"))
      (node (ref "C15") (pin "1") (pinfunction "1_1") (pintype "passive"))
      (node (ref "C152") (pin "1") (pinfunction "1_1") (pintype "passive"))
      (node (ref "C16") (pin "1") (pinfunction "1_1") (pintype "passive"))
      (node (ref "C17") (pin "1") (pinfunction "1_1") (pintype "passive"))
      (node (ref "C18") (pin "1") (pinfunction "1_1") (pintype "passive"))
      (node (ref "C19") (pin "1") (pinfunction "1_1") (pintype "passive"))
      (node (ref "C2") (pin "1") (pinfunction "1_1") (pintype "passive"))
      (node (ref "C20") (pin "1") (pinfunction "1_1") (pintype "passive"))
      (node (ref "C21") (pin "1") (pinfunction "1_1") (pintype "passive"))
      (node (ref "C22") (pin "1") (pinfunction "1_1") (pintype "passive"))
      (node (ref "C23") (pin "1") (pinfunction "1_1") (pintype "passive"))
      (node (ref "C24") (pin "2") (pinfunction "2_2") (pintype "passive"))
      (node (ref "C25") (pin "2") (pinfunction "2_2") (pintype "passive"))
      (node (ref "C26") (pin "1") (pinfunction "1_1") (pintype "passive"))
      (node (ref "C27") (pin "1") (pinfunction "1_1") (pintype "passive"))
      (node (ref "C28") (pin "2") (pinfunction "2_2") (pintype "passive"))
      (node (ref "C29") (pin "2") (pinfunction "2_2") (pintype "passive"))
      (node (ref "C3") (pin "1") (pinfunction "1_1") (pintype "passive"))
      (node (ref "C30") (pin "1") (pinfunction "1_1") (pintype "passive"))
      (node (ref "C31") (pin "1") (pinfunction "1_1") (pintype "passive"))
      (node (ref "C32") (pin "2") (pinfunction "2_2") (pintype "passive"))
      (node (ref "C33") (pin "2") (pinfunction "2_2") (pintype "passive"))
      (node (ref "C34") (pin "1") (pinfunction "1_1") (pintype "passive"))
      (node (ref "C35") (pin "1") (pinfunction "1_1") (pintype "passive"))
      (node (ref "C36") (pin "2") (pinfunction "2_2") (pintype "passive"))
      (node (ref "C37") (pin "2") (pinfunction "2_2") (pintype "passive"))
      (node (ref "C4") (pin "1") (pinfunction "1_1") (pintype "passive"))
      (node (ref "C40") (pin "1") (pinfunction "1_1") (pintype "passive"))
      (node (ref "C41") (pin "1") (pinfunction "1_1") (pintype "passive"))
      (node (ref "C42") (pin "1") (pinfunction "1_1") (pintype "passive"))
      (node (ref "C43") (pin "1") (pinfunction "1_1") (pintype "passive"))
      (node (ref "C44") (pin "1") (pinfunction "1_1") (pintype "passive"))
      (node (ref "C45") (pin "1") (pinfunction "1_1") (pintype "passive"))
      (node (ref "C46") (pin "1") (pinfunction "1_1") (pintype "passive"))
      (node (ref "C47") (pin "1") (pinfunction "1_1") (pintype "passive"))
      (node (ref "C48") (pin "1") (pinfunction "1_1") (pintype "passive"))
      (node (ref "C49") (pin "1") (pinfunction "1_1") (pintype "passive"))
      (node (ref "C5") (pin "1") (pinfunction "1_1") (pintype "passive"))
      (node (ref "C6") (pin "1") (pinfunction "1_1") (pintype "passive"))
      (node (ref "C7") (pin "1") (pinfunction "1_1") (pintype "passive"))
      (node (ref "C8") (pin "1") (pinfunction "1_1") (pintype "passive"))
      (node (ref "C9") (pin "1") (pinfunction "1_1") (pintype "passive"))
      (node (ref "DPOT1") (pin "4") (pinfunction "GND_4") (pintype "passive"))
      (node (ref "DPOT2") (pin "4") (pinfunction "GND_4") (pintype "passive"))
      (node (ref "DPOT3") (pin "4") (pinfunction "GND_4") (pintype "passive"))
      (node (ref "LED1") (pin "2") (pinfunction "2_2") (pintype "passive"))
      (node (ref "LED2") (pin "2") (pinfunction "2_2") (pintype "passive"))
      (node (ref "LED3") (pin "2") (pinfunction "2_2") (pintype "passive"))
      (node (ref "LED4") (pin "2") (pinfunction "2_2") (pintype "passive"))
      (node (ref "P4") (pin "3") (pinfunction "3_3") (pintype "passive"))
      (node (ref "P5") (pin "1") (pinfunction "1_1") (pintype "passive"))
      (node (ref "P6") (pin "1") (pinfunction "1_1") (pintype "passive"))
      (node (ref "P7") (pin "1") (pinfunction "1_1") (pintype "passive"))
      (node (ref "P8") (pin "1") (pinfunction "1_1") (pintype "passive"))
      (node (ref "R10") (pin "1") (pinfunction "1_1") (pintype "passive"))
      (node (ref "R11") (pin "1") (pinfunction "1_1") (pintype "passive"))
      (node (ref "R12") (pin "1") (pinfunction "1_1") (pintype "passive"))
      (node (ref "R13") (pin "1") (pinfunction "1_1") (pintype "passive"))
      (node (ref "R9") (pin "1") (pinfunction "1_1") (pintype "passive"))
      (node (ref "REG1") (pin "3") (pinfunction "GND_3") (pintype "passive"))
      (node (ref "REG1") (pin "6") (pinfunction "GND_6") (pintype "passive"))
      (node (ref "REG2") (pin "3") (pinfunction "GND_3") (pintype "passive"))
      (node (ref "REG2") (pin "6") (pinfunction "GND_6") (pintype "passive"))
      (node (ref "REG3") (pin "3") (pinfunction "GND_3") (pintype "passive"))
      (node (ref "REG3") (pin "6") (pinfunction "GND_6") (pintype "passive"))
      (node (ref "REG4") (pin "3") (pinfunction "GND_3") (pintype "passive"))
      (node (ref "REG4") (pin "6") (pinfunction "GND_6") (pintype "passive"))
      (node (ref "REG5") (pin "3") (pinfunction "GND_3") (pintype "passive"))
      (node (ref "REG5") (pin "6") (pinfunction "GND_6") (pintype "passive"))
      (node (ref "U33") (pin "1") (pinfunction "1~{OE}_1") (pintype "passive"))
      (node (ref "U33") (pin "10") (pinfunction "GND_10") (pintype "passive"))
      (node (ref "U33") (pin "19") (pinfunction "2~{OE}_19") (pintype "passive"))
    )
    (net (code "41") (name "/IFLAG1") (class "Default")
      (node (ref "R8") (pin "1") (pinfunction "1_1") (pintype "passive"))
      (node (ref "U1") (pin "8") (pinfunction "IFLAG_8") (pintype "passive"))
    )
    (net (code "42") (name "/IFLAG2") (class "Default")
      (node (ref "R7") (pin "1") (pinfunction "1_1") (pintype "passive"))
      (node (ref "U2") (pin "8") (pinfunction "IFLAG_8") (pintype "passive"))
    )
    (net (code "43") (name "/IFLAG3") (class "Default")
      (node (ref "R6") (pin "1") (pinfunction "1_1") (pintype "passive"))
      (node (ref "U3") (pin "8") (pinfunction "IFLAG_8") (pintype "passive"))
    )
    (net (code "44") (name "/IFLAG4") (class "Default")
      (node (ref "R5") (pin "1") (pinfunction "1_1") (pintype "passive"))
      (node (ref "U4") (pin "8") (pinfunction "IFLAG_8") (pintype "passive"))
    )
    (net (code "45") (name "/ISET1") (class "Default")
      (node (ref "R62") (pin "2") (pinfunction "2_2") (pintype "passive"))
      (node (ref "U1") (pin "9") (pinfunction "ISET_9") (pintype "passive"))
    )
    (net (code "46") (name "/ISET2") (class "Default")
      (node (ref "R67") (pin "2") (pinfunction "2_2") (pintype "passive"))
      (node (ref "U2") (pin "9") (pinfunction "ISET_9") (pintype "passive"))
    )
    (net (code "47") (name "/ISET3") (class "Default")
      (node (ref "R72") (pin "2") (pinfunction "2_2") (pintype "passive"))
      (node (ref "U3") (pin "9") (pinfunction "ISET_9") (pintype "passive"))
    )
    (net (code "48") (name "/ISET4") (class "Default")
      (node (ref "R77") (pin "2") (pinfunction "2_2") (pintype "passive"))
      (node (ref "U4") (pin "9") (pinfunction "ISET_9") (pintype "passive"))
    )
    (net (code "49") (name "/OUT1") (class "Default")
      (node (ref "P9") (pin "10") (pinfunction "10_10") (pintype "passive"))
      (node (ref "P9") (pin "2") (pinfunction "2_2") (pintype "passive"))
      (node (ref "P9") (pin "4") (pinfunction "4_4") (pintype "passive"))
      (node (ref "P9") (pin "6") (pinfunction "6_6") (pintype "passive"))
      (node (ref "P9") (pin "8") (pinfunction "8_8") (pintype "passive"))
    )
    (net (code "50") (name "/OUT2") (class "Default")
      (node (ref "P10") (pin "10") (pinfunction "10_10") (pintype "passive"))
      (node (ref "P10") (pin "2") (pinfunction "2_2") (pintype "passive"))
      (node (ref "P10") (pin "4") (pinfunction "4_4") (pintype "passive"))
      (node (ref "P10") (pin "6") (pinfunction "6_6") (pintype "passive"))
      (node (ref "P10") (pin "8") (pinfunction "8_8") (pintype "passive"))
    )
    (net (code "51") (name "/OUT3") (class "Default")
      (node (ref "P11") (pin "10") (pinfunction "10_10") (pintype "passive"))
      (node (ref "P11") (pin "2") (pinfunction "2_2") (pintype "passive"))
      (node (ref "P11") (pin "4") (pinfunction "4_4") (pintype "passive"))
      (node (ref "P11") (pin "6") (pinfunction "6_6") (pintype "passive"))
      (node (ref "P11") (pin "8") (pinfunction "8_8") (pintype "passive"))
    )
    (net (code "52") (name "/OUT4") (class "Default")
      (node (ref "P12") (pin "10") (pinfunction "10_10") (pintype "passive"))
      (node (ref "P12") (pin "2") (pinfunction "2_2") (pintype "passive"))
      (node (ref "P12") (pin "4") (pinfunction "4_4") (pintype "passive"))
      (node (ref "P12") (pin "6") (pinfunction "6_6") (pintype "passive"))
      (node (ref "P12") (pin "8") (pinfunction "8_8") (pintype "passive"))
    )
    (net (code "53") (name "/OUT5") (class "Default")
      (node (ref "P13") (pin "10") (pinfunction "10_10") (pintype "passive"))
      (node (ref "P13") (pin "2") (pinfunction "2_2") (pintype "passive"))
      (node (ref "P13") (pin "4") (pinfunction "4_4") (pintype "passive"))
      (node (ref "P13") (pin "6") (pinfunction "6_6") (pintype "passive"))
      (node (ref "P13") (pin "8") (pinfunction "8_8") (pintype "passive"))
    )
    (net (code "54") (name "/OUT6") (class "Default")
      (node (ref "P14") (pin "10") (pinfunction "10_10") (pintype "passive"))
      (node (ref "P14") (pin "2") (pinfunction "2_2") (pintype "passive"))
      (node (ref "P14") (pin "4") (pinfunction "4_4") (pintype "passive"))
      (node (ref "P14") (pin "6") (pinfunction "6_6") (pintype "passive"))
      (node (ref "P14") (pin "8") (pinfunction "8_8") (pintype "passive"))
    )
    (net (code "55") (name "/OUT7") (class "Default")
      (node (ref "P15") (pin "10") (pinfunction "10_10") (pintype "passive"))
      (node (ref "P15") (pin "2") (pinfunction "2_2") (pintype "passive"))
      (node (ref "P15") (pin "4") (pinfunction "4_4") (pintype "passive"))
      (node (ref "P15") (pin "6") (pinfunction "6_6") (pintype "passive"))
      (node (ref "P15") (pin "8") (pinfunction "8_8") (pintype "passive"))
    )
    (net (code "56") (name "/OUT8") (class "Default")
      (node (ref "P16") (pin "10") (pinfunction "10_10") (pintype "passive"))
      (node (ref "P16") (pin "2") (pinfunction "2_2") (pintype "passive"))
      (node (ref "P16") (pin "4") (pinfunction "4_4") (pintype "passive"))
      (node (ref "P16") (pin "6") (pinfunction "6_6") (pintype "passive"))
      (node (ref "P16") (pin "8") (pinfunction "8_8") (pintype "passive"))
    )
    (net (code "57") (name "/OUTM1") (class "Default")
      (node (ref "R39") (pin "2") (pinfunction "2_2") (pintype "passive"))
    )
    (net (code "58") (name "/OUTM2") (class "Default")
      (node (ref "R45") (pin "2") (pinfunction "2_2") (pintype "passive"))
    )
    (net (code "59") (name "/OUTM3") (class "Default")
      (node (ref "R51") (pin "2") (pinfunction "2_2") (pintype "passive"))
    )
    (net (code "60") (name "/OUTM4") (class "Default")
      (node (ref "R57") (pin "2") (pinfunction "2_2") (pintype "passive"))
    )
    (net (code "61") (name "/OUTM5") (class "Default")
      (node (ref "R15") (pin "2") (pinfunction "2_2") (pintype "passive"))
    )
    (net (code "62") (name "/OUTM6") (class "Default")
      (node (ref "R27") (pin "2") (pinfunction "2_2") (pintype "passive"))
    )
    (net (code "63") (name "/OUTM7") (class "Default")
      (node (ref "R21") (pin "2") (pinfunction "2_2") (pintype "passive"))
    )
    (net (code "64") (name "/OUTM8") (class "Default")
      (node (ref "R33") (pin "2") (pinfunction "2_2") (pintype "passive"))
    )
    (net (code "66") (name "/OUTP1") (class "Default")
      (node (ref "R38") (pin "2") (pinfunction "2_2") (pintype "passive"))
    )
    (net (code "67") (name "/OUTP2") (class "Default")
      (node (ref "R44") (pin "2") (pinfunction "2_2") (pintype "passive"))
    )
    (net (code "68") (name "/OUTP3") (class "Default")
      (node (ref "R50") (pin "2") (pinfunction "2_2") (pintype "passive"))
    )
    (net (code "69") (name "/OUTP4") (class "Default")
      (node (ref "R56") (pin "2") (pinfunction "2_2") (pintype "passive"))
    )
    (net (code "70") (name "/OUTP5") (class "Default")
      (node (ref "R14") (pin "2") (pinfunction "2_2") (pintype "passive"))
    )
    (net (code "71") (name "/OUTP6") (class "Default")
      (node (ref "R26") (pin "2") (pinfunction "2_2") (pintype "passive"))
    )
    (net (code "72") (name "/OUTP7") (class "Default")
      (node (ref "R20") (pin "2") (pinfunction "2_2") (pintype "passive"))
    )
    (net (code "73") (name "/OUTP8") (class "Default")
      (node (ref "R32") (pin "2") (pinfunction "2_2") (pintype "passive"))
    )
    (net (code "76") (name "/SPI_CLK") (class "Default")
      (node (ref "DPOT1") (pin "6") (pinfunction "CLK_6") (pintype "passive"))
      (node (ref "DPOT2") (pin "6") (pinfunction "CLK_6") (pintype "passive"))
      (node (ref "DPOT3") (pin "6") (pinfunction "CLK_6") (pintype "passive"))
    )
    (net (code "77") (name "/SPI_CS3") (class "Default")
      (node (ref "DPOT1") (pin "8") (pinfunction "~{CS}_8") (pintype "passive"))
    )
    (net (code "78") (name "/SPI_CS4") (class "Default")
      (node (ref "DPOT2") (pin "8") (pinfunction "~{CS}_8") (pintype "passive"))
    )
    (net (code "79") (name "/SPI_CS5") (class "Default")
      (node (ref "DPOT3") (pin "8") (pinfunction "~{CS}_8") (pintype "passive"))
    )
    (net (code "81") (name "/SPI_DIN") (class "Default")
      (node (ref "DPOT1") (pin "7") (pinfunction "SDI_7") (pintype "passive"))
      (node (ref "DPOT2") (pin "7") (pinfunction "SDI_7") (pintype "passive"))
      (node (ref "DPOT3") (pin "7") (pinfunction "SDI_7") (pintype "passive"))
    )
    (net (code "82") (name "/TFLAG1") (class "Default")
      (node (ref "R4") (pin "1") (pinfunction "1_1") (pintype "passive"))
      (node (ref "U1") (pin "3") (pinfunction "TFLAG_3") (pintype "passive"))
    )
    (net (code "83") (name "/TFLAG2") (class "Default")
      (node (ref "R3") (pin "1") (pinfunction "1_1") (pintype "passive"))
      (node (ref "U2") (pin "3") (pinfunction "TFLAG_3") (pintype "passive"))
    )
    (net (code "84") (name "/TFLAG3") (class "Default")
      (node (ref "R2") (pin "1") (pinfunction "1_1") (pintype "passive"))
      (node (ref "U3") (pin "3") (pinfunction "TFLAG_3") (pintype "passive"))
    )
    (net (code "85") (name "/TFLAG4") (class "Default")
      (node (ref "R1") (pin "1") (pinfunction "1_1") (pintype "passive"))
      (node (ref "U4") (pin "3") (pinfunction "TFLAG_3") (pintype "passive"))
    )
    (net (code "86") (name "/VI1") (class "Default")
      (node (ref "C22") (pin "2") (pinfunction "2_2") (pintype "passive"))
      (node (ref "C23") (pin "2") (pinfunction "2_2") (pintype "passive"))
      (node (ref "C3") (pin "2") (pinfunction "2_2") (pintype "passive"))
      (node (ref "DPOT1") (pin "1") (pinfunction "B1_1") (pintype "passive"))
      (node (ref "R250") (pin "1") (pinfunction "1_1") (pintype "passive"))
      (node (ref "REG1") (pin "2") (pinfunction "OUT_2") (pintype "passive"))
      (node (ref "U1") (pin "17") (pinfunction "V+PWR_17") (pintype "passive"))
      (node (ref "U1") (pin "18") (pinfunction "V+PWR_18") (pintype "passive"))
      (node (ref "U1") (pin "19") (pinfunction "V+PWR_19") (pintype "passive"))
      (node (ref "U1") (pin "2") (pinfunction "V+_2") (pintype "passive"))
    )
    (net (code "87") (name "/VI2") (class "Default")
      (node (ref "C26") (pin "2") (pinfunction "2_2") (pintype "passive"))
      (node (ref "C27") (pin "2") (pinfunction "2_2") (pintype "passive"))
      (node (ref "C6") (pin "2") (pinfunction "2_2") (pintype "passive"))
      (node (ref "DPOT1") (pin "9") (pinfunction "B2_9") (pintype "passive"))
      (node (ref "R256") (pin "1") (pinfunction "1_1") (pintype "passive"))
      (node (ref "REG2") (pin "2") (pinfunction "OUT_2") (pintype "passive"))
      (node (ref "U2") (pin "17") (pinfunction "V+PWR_17") (pintype "passive"))
      (node (ref "U2") (pin "18") (pinfunction "V+PWR_18") (pintype "passive"))
      (node (ref "U2") (pin "19") (pinfunction "V+PWR_19") (pintype "passive"))
      (node (ref "U2") (pin "2") (pinfunction "V+_2") (pintype "passive"))
    )
    (net (code "88") (name "/VI3") (class "Default")
      (node (ref "C30") (pin "2") (pinfunction "2_2") (pintype "passive"))
      (node (ref "C31") (pin "2") (pinfunction "2_2") (pintype "passive"))
      (node (ref "C9") (pin "2") (pinfunction "2_2") (pintype "passive"))
      (node (ref "DPOT2") (pin "1") (pinfunction "B1_1") (pintype "passive"))
      (node (ref "R261") (pin "1") (pinfunction "1_1") (pintype "passive"))
      (node (ref "REG3") (pin "2") (pinfunction "OUT_2") (pintype "passive"))
      (node (ref "U3") (pin "17") (pinfunction "V+PWR_17") (pintype "passive"))
      (node (ref "U3") (pin "18") (pinfunction "V+PWR_18") (pintype "passive"))
      (node (ref "U3") (pin "19") (pinfunction "V+PWR_19") (pintype "passive"))
      (node (ref "U3") (pin "2") (pinfunction "V+_2") (pintype "passive"))
    )
    (net (code "89") (name "/VI4") (class "Default")
      (node (ref "C12") (pin "2") (pinfunction "2_2") (pintype "passive"))
      (node (ref "C34") (pin "2") (pinfunction "2_2") (pintype "passive"))
      (node (ref "C35") (pin "2") (pinfunction "2_2") (pintype "passive"))
      (node (ref "DPOT2") (pin "9") (pinfunction "B2_9") (pintype "passive"))
      (node (ref "R265") (pin "1") (pinfunction "1_1") (pintype "passive"))
      (node (ref "REG4") (pin "2") (pinfunction "OUT_2") (pintype "passive"))
      (node (ref "U4") (pin "17") (pinfunction "V+PWR_17") (pintype "passive"))
      (node (ref "U4") (pin "18") (pinfunction "V+PWR_18") (pintype "passive"))
      (node (ref "U4") (pin "19") (pinfunction "V+PWR_19") (pintype "passive"))
      (node (ref "U4") (pin "2") (pinfunction "V+_2") (pintype "passive"))
    )
    (net (code "90") (name "/VMINUS1") (class "Default")
      (node (ref "D1") (pin "2") (pinfunction "C2_2") (pintype "passive"))
      (node (ref "D1") (pin "4") (pinfunction "A1_4") (pintype "passive"))
      (node (ref "R39") (pin "1") (pinfunction "1_1") (pintype "passive"))
      (node (ref "R40") (pin "1") (pinfunction "1_1") (pintype "passive"))
      (node (ref "U1") (pin "6") (pinfunction "IN-_6") (pintype "passive"))
    )
    (net (code "91") (name "/VMINUS2") (class "Default")
      (node (ref "D2") (pin "2") (pinfunction "C2_2") (pintype "passive"))
      (node (ref "D2") (pin "4") (pinfunction "A1_4") (pintype "passive"))
      (node (ref "R45") (pin "1") (pinfunction "1_1") (pintype "passive"))
      (node (ref "R46") (pin "1") (pinfunction "1_1") (pintype "passive"))
      (node (ref "U2") (pin "6") (pinfunction "IN-_6") (pintype "passive"))
    )
    (net (code "92") (name "/VMINUS3") (class "Default")
      (node (ref "D3") (pin "2") (pinfunction "C2_2") (pintype "passive"))
      (node (ref "D3") (pin "4") (pinfunction "A1_4") (pintype "passive"))
      (node (ref "R51") (pin "1") (pinfunction "1_1") (pintype "passive"))
      (node (ref "R52") (pin "1") (pinfunction "1_1") (pintype "passive"))
      (node (ref "U3") (pin "6") (pinfunction "IN-_6") (pintype "passive"))
    )
    (net (code "93") (name "/VMINUS4") (class "Default")
      (node (ref "D4") (pin "2") (pinfunction "C2_2") (pintype "passive"))
      (node (ref "D4") (pin "4") (pinfunction "A1_4") (pintype "passive"))
      (node (ref "R57") (pin "1") (pinfunction "1_1") (pintype "passive"))
      (node (ref "R58") (pin "1") (pinfunction "1_1") (pintype "passive"))
      (node (ref "U4") (pin "6") (pinfunction "IN-_6") (pintype "passive"))
    )
    (net (code "94") (name "/VMINUS5") (class "Default")
      (node (ref "R15") (pin "1") (pinfunction "1_1") (pintype "passive"))
      (node (ref "R16") (pin "1") (pinfunction "1_1") (pintype "passive"))
      (node (ref "U5") (pin "2") (pinfunction "1IN-_2") (pintype "passive"))
    )
    (net (code "95") (name "/VMINUS6") (class "Default")
      (node (ref "R27") (pin "1") (pinfunction "1_1") (pintype "passive"))
      (node (ref "R28") (pin "1") (pinfunction "1_1") (pintype "passive"))
      (node (ref "U5") (pin "8") (pinfunction "2IN-_8") (pintype "passive"))
    )
    (net (code "96") (name "/VMINUS7") (class "Default")
      (node (ref "R21") (pin "1") (pinfunction "1_1") (pintype "passive"))
      (node (ref "R22") (pin "1") (pinfunction "1_1") (pintype "passive"))
      (node (ref "U6") (pin "2") (pinfunction "1IN-_2") (pintype "passive"))
    )
    (net (code "97") (name "/VMINUS8") (class "Default")
      (node (ref "R33") (pin "1") (pinfunction "1_1") (pintype "passive"))
      (node (ref "R34") (pin "1") (pinfunction "1_1") (pintype "passive"))
      (node (ref "U6") (pin "8") (pinfunction "2IN-_8") (pintype "passive"))
    )
    (net (code "98") (name "/VN1") (class "Default")
      (node (ref "C24") (pin "1") (pinfunction "1_1") (pintype "passive"))
      (node (ref "C25") (pin "1") (pinfunction "1_1") (pintype "passive"))
      (node (ref "P5") (pin "3") (pinfunction "3_3") (pintype "passive"))
    )
    (net (code "99") (name "/VN2") (class "Default")
      (node (ref "C28") (pin "1") (pinfunction "1_1") (pintype "passive"))
      (node (ref "C29") (pin "1") (pinfunction "1_1") (pintype "passive"))
      (node (ref "P6") (pin "3") (pinfunction "3_3") (pintype "passive"))
    )
    (net (code "100") (name "/VN3") (class "Default")
      (node (ref "C32") (pin "1") (pinfunction "1_1") (pintype "passive"))
      (node (ref "C33") (pin "1") (pinfunction "1_1") (pintype "passive"))
      (node (ref "P7") (pin "3") (pinfunction "3_3") (pintype "passive"))
    )
    (net (code "101") (name "/VN4") (class "Default")
      (node (ref "C36") (pin "1") (pinfunction "1_1") (pintype "passive"))
      (node (ref "C37") (pin "1") (pinfunction "1_1") (pintype "passive"))
      (node (ref "P8") (pin "3") (pinfunction "3_3") (pintype "passive"))
    )
    (net (code "102") (name "/VN5") (class "Default")
      (node (ref "C40") (pin "2") (pinfunction "2_2") (pintype "passive"))
      (node (ref "C41") (pin "2") (pinfunction "2_2") (pintype "passive"))
      (node (ref "P4") (pin "5") (pinfunction "5_5") (pintype "passive"))
    )
    (net (code "104") (name "/VO1") (class "Default")
      (node (ref "R40") (pin "2") (pinfunction "2_2") (pintype "passive"))
      (node (ref "R43") (pin "1") (pinfunction "1_1") (pintype "passive"))
      (node (ref "TP20") (pin "1") (pinfunction "TP_1") (pintype "passive"))
      (node (ref "U1") (pin "15") (pinfunction "VOUT_15") (pintype "passive"))
      (node (ref "U1") (pin "16") (pinfunction "VOUT_16") (pintype "passive"))
    )
    (net (code "105") (name "/VO2") (class "Default")
      (node (ref "R46") (pin "2") (pinfunction "2_2") (pintype "passive"))
      (node (ref "R49") (pin "1") (pinfunction "1_1") (pintype "passive"))
      (node (ref "U2") (pin "15") (pinfunction "VOUT_15") (pintype "passive"))
      (node (ref "U2") (pin "16") (pinfunction "VOUT_16") (pintype "passive"))
    )
    (net (code "106") (name "/VO3") (class "Default")
      (node (ref "R52") (pin "2") (pinfunction "2_2") (pintype "passive"))
      (node (ref "R55") (pin "1") (pinfunction "1_1") (pintype "passive"))
      (node (ref "U3") (pin "15") (pinfunction "VOUT_15") (pintype "passive"))
      (node (ref "U3") (pin "16") (pinfunction "VOUT_16") (pintype "passive"))
    )
    (net (code "107") (name "/VO4") (class "Default")
      (node (ref "R58") (pin "2") (pinfunction "2_2") (pintype "passive"))
      (node (ref "R61") (pin "1") (pinfunction "1_1") (pintype "passive"))
      (node (ref "U4") (pin "15") (pinfunction "VOUT_15") (pintype "passive"))
      (node (ref "U4") (pin "16") (pinfunction "VOUT_16") (pintype "passive"))
    )
    (net (code "108") (name "/VO5") (class "Default")
      (node (ref "R16") (pin "2") (pinfunction "2_2") (pintype "passive"))
      (node (ref "R19") (pin "1") (pinfunction "1_1") (pintype "passive"))
      (node (ref "U5") (pin "1") (pinfunction "1OUT_1") (pintype "passive"))
    )
    (net (code "109") (name "/VO6") (class "Default")
      (node (ref "R28") (pin "2") (pinfunction "2_2") (pintype "passive"))
      (node (ref "R31") (pin "1") (pinfunction "1_1") (pintype "passive"))
      (node (ref "U5") (pin "9") (pinfunction "2OUT_9") (pintype "passive"))
    )
    (net (code "110") (name "/VO7") (class "Default")
      (node (ref "R22") (pin "2") (pinfunction "2_2") (pintype "passive"))
      (node (ref "R25") (pin "1") (pinfunction "1_1") (pintype "passive"))
      (node (ref "U6") (pin "1") (pinfunction "1OUT_1") (pintype "passive"))
    )
    (net (code "111") (name "/VO8") (class "Default")
      (node (ref "R34") (pin "2") (pinfunction "2_2") (pintype "passive"))
      (node (ref "R37") (pin "1") (pinfunction "1_1") (pintype "passive"))
      (node (ref "U6") (pin "9") (pinfunction "2OUT_9") (pintype "passive"))
    )
    (net (code "112") (name "/VOUT1") (class "Default")
      (node (ref "P9") (pin "1") (pinfunction "1_1") (pintype "passive"))
      (node (ref "R42") (pin "2") (pinfunction "2_2") (pintype "passive"))
      (node (ref "R43") (pin "2") (pinfunction "2_2") (pintype "passive"))
      (node (ref "R63") (pin "2") (pinfunction "2_2") (pintype "passive"))
      (node (ref "R64") (pin "2") (pinfunction "2_2") (pintype "passive"))
      (node (ref "R65") (pin "2") (pinfunction "2_2") (pintype "passive"))
      (node (ref "R66") (pin "2") (pinfunction "2_2") (pintype "passive"))
      (node (ref "TP18") (pin "1") (pinfunction "TP_1") (pintype "passive"))
    )
    (net (code "113") (name "/VOUT2") (class "Default")
      (node (ref "P10") (pin "1") (pinfunction "1_1") (pintype "passive"))
      (node (ref "R48") (pin "2") (pinfunction "2_2") (pintype "passive"))
      (node (ref "R49") (pin "2") (pinfunction "2_2") (pintype "passive"))
      (node (ref "R68") (pin "2") (pinfunction "2_2") (pintype "passive"))
      (node (ref "R69") (pin "2") (pinfunction "2_2") (pintype "passive"))
      (node (ref "R70") (pin "2") (pinfunction "2_2") (pintype "passive"))
      (node (ref "R71") (pin "2") (pinfunction "2_2") (pintype "passive"))
    )
    (net (code "114") (name "/VOUT3") (class "Default")
      (node (ref "P11") (pin "1") (pinfunction "1_1") (pintype "passive"))
      (node (ref "R54") (pin "2") (pinfunction "2_2") (pintype "passive"))
      (node (ref "R55") (pin "2") (pinfunction "2_2") (pintype "passive"))
      (node (ref "R73") (pin "2") (pinfunction "2_2") (pintype "passive"))
      (node (ref "R74") (pin "2") (pinfunction "2_2") (pintype "passive"))
      (node (ref "R75") (pin "2") (pinfunction "2_2") (pintype "passive"))
      (node (ref "R76") (pin "2") (pinfunction "2_2") (pintype "passive"))
    )
    (net (code "115") (name "/VOUT4") (class "Default")
      (node (ref "P12") (pin "1") (pinfunction "1_1") (pintype "passive"))
      (node (ref "R60") (pin "2") (pinfunction "2_2") (pintype "passive"))
      (node (ref "R61") (pin "2") (pinfunction "2_2") (pintype "passive"))
      (node (ref "R78") (pin "2") (pinfunction "2_2") (pintype "passive"))
      (node (ref "R79") (pin "2") (pinfunction "2_2") (pintype "passive"))
      (node (ref "R80") (pin "2") (pinfunction "2_2") (pintype "passive"))
      (node (ref "R81") (pin "2") (pinfunction "2_2") (pintype "passive"))
    )
    (net (code "116") (name "/VOUT5") (class "Default")
      (node (ref "P13") (pin "1") (pinfunction "1_1") (pintype "passive"))
      (node (ref "R18") (pin "2") (pinfunction "2_2") (pintype "passive"))
      (node (ref "R19") (pin "2") (pinfunction "2_2") (pintype "passive"))
      (node (ref "R82") (pin "2") (pinfunction "2_2") (pintype "passive"))
      (node (ref "R83") (pin "2") (pinfunction "2_2") (pintype "passive"))
      (node (ref "R84") (pin "2") (pinfunction "2_2") (pintype "passive"))
      (node (ref "R85") (pin "2") (pinfunction "2_2") (pintype "passive"))
    )
    (net (code "117") (name "/VOUT6") (class "Default")
      (node (ref "P14") (pin "1") (pinfunction "1_1") (pintype "passive"))
      (node (ref "R30") (pin "2") (pinfunction "2_2") (pintype "passive"))
      (node (ref "R31") (pin "2") (pinfunction "2_2") (pintype "passive"))
      (node (ref "R86") (pin "2") (pinfunction "2_2") (pintype "passive"))
      (node (ref "R87") (pin "2") (pinfunction "2_2") (pintype "passive"))
      (node (ref "R88") (pin "2") (pinfunction "2_2") (pintype "passive"))
      (node (ref "R89") (pin "2") (pinfunction "2_2") (pintype "passive"))
    )
    (net (code "118") (name "/VOUT7") (class "Default")
      (node (ref "P15") (pin "1") (pinfunction "1_1") (pintype "passive"))
      (node (ref "R24") (pin "2") (pinfunction "2_2") (pintype "passive"))
      (node (ref "R25") (pin "2") (pinfunction "2_2") (pintype "passive"))
      (node (ref "R90") (pin "2") (pinfunction "2_2") (pintype "passive"))
      (node (ref "R91") (pin "2") (pinfunction "2_2") (pintype "passive"))
      (node (ref "R92") (pin "2") (pinfunction "2_2") (pintype "passive"))
      (node (ref "R93") (pin "2") (pinfunction "2_2") (pintype "passive"))
    )
    (net (code "119") (name "/VOUT8") (class "Default")
      (node (ref "P16") (pin "1") (pinfunction "1_1") (pintype "passive"))
      (node (ref "R36") (pin "2") (pinfunction "2_2") (pintype "passive"))
      (node (ref "R37") (pin "2") (pinfunction "2_2") (pintype "passive"))
      (node (ref "R94") (pin "2") (pinfunction "2_2") (pintype "passive"))
      (node (ref "R95") (pin "2") (pinfunction "2_2") (pintype "passive"))
      (node (ref "R96") (pin "2") (pinfunction "2_2") (pintype "passive"))
      (node (ref "R97") (pin "2") (pinfunction "2_2") (pintype "passive"))
    )
    (net (code "122") (name "/VPLUS1") (class "Default")
      (node (ref "D1") (pin "1") (pinfunction "C1_1") (pintype "passive"))
      (node (ref "D1") (pin "3") (pinfunction "A2_3") (pintype "passive"))
      (node (ref "R38") (pin "1") (pinfunction "1_1") (pintype "passive"))
      (node (ref "R41") (pin "2") (pinfunction "2_2") (pintype "passive"))
      (node (ref "U1") (pin "5") (pinfunction "IN+_5") (pintype "passive"))
    )
    (net (code "123") (name "/VPLUS2") (class "Default")
      (node (ref "D2") (pin "1") (pinfunction "C1_1") (pintype "passive"))
      (node (ref "D2") (pin "3") (pinfunction "A2_3") (pintype "passive"))
      (node (ref "R44") (pin "1") (pinfunction "1_1") (pintype "passive"))
      (node (ref "R47") (pin "2") (pinfunction "2_2") (pintype "passive"))
      (node (ref "U2") (pin "5") (pinfunction "IN+_5") (pintype "passive"))
    )
    (net (code "124") (name "/VPLUS3") (class "Default")
      (node (ref "D3") (pin "1") (pinfunction "C1_1") (pintype "passive"))
      (node (ref "D3") (pin "3") (pinfunction "A2_3") (pintype "passive"))
      (node (ref "R50") (pin "1") (pinfunction "1_1") (pintype "passive"))
      (node (ref "R53") (pin "2") (pinfunction "2_2") (pintype "passive"))
      (node (ref "U3") (pin "5") (pinfunction "IN+_5") (pintype "passive"))
    )
    (net (code "125") (name "/VPLUS4") (class "Default")
      (node (ref "D4") (pin "1") (pinfunction "C1_1") (pintype "passive"))
      (node (ref "D4") (pin "3") (pinfunction "A2_3") (pintype "passive"))
      (node (ref "R56") (pin "1") (pinfunction "1_1") (pintype "passive"))
      (node (ref "R59") (pin "2") (pinfunction "2_2") (pintype "passive"))
      (node (ref "U4") (pin "5") (pinfunction "IN+_5") (pintype "passive"))
    )
    (net (code "126") (name "/VPLUS5") (class "Default")
      (node (ref "R14") (pin "1") (pinfunction "1_1") (pintype "passive"))
      (node (ref "R17") (pin "2") (pinfunction "2_2") (pintype "passive"))
      (node (ref "U5") (pin "3") (pinfunction "1IN+_3") (pintype "passive"))
    )
    (net (code "127") (name "/VPLUS6") (class "Default")
      (node (ref "R26") (pin "1") (pinfunction "1_1") (pintype "passive"))
      (node (ref "R29") (pin "2") (pinfunction "2_2") (pintype "passive"))
      (node (ref "U5") (pin "7") (pinfunction "2IN+_7") (pintype "passive"))
    )
    (net (code "128") (name "/VPLUS7") (class "Default")
      (node (ref "R20") (pin "1") (pinfunction "1_1") (pintype "passive"))
      (node (ref "R23") (pin "2") (pinfunction "2_2") (pintype "passive"))
      (node (ref "U6") (pin "3") (pinfunction "1IN+_3") (pintype "passive"))
    )
    (net (code "129") (name "/VPLUS8") (class "Default")
      (node (ref "R32") (pin "1") (pinfunction "1_1") (pintype "passive"))
      (node (ref "R35") (pin "2") (pinfunction "2_2") (pintype "passive"))
      (node (ref "U6") (pin "7") (pinfunction "2IN+_7") (pintype "passive"))
    )
    (net (code "130") (name "/VR") (class "Default")
      (node (ref "C15") (pin "2") (pinfunction "2_2") (pintype "passive"))
      (node (ref "C42") (pin "2") (pinfunction "2_2") (pintype "passive"))
      (node (ref "C43") (pin "2") (pinfunction "2_2") (pintype "passive"))
      (node (ref "C46") (pin "2") (pinfunction "2_2") (pintype "passive"))
      (node (ref "C47") (pin "2") (pinfunction "2_2") (pintype "passive"))
      (node (ref "DPOT3") (pin "1") (pinfunction "B1_1") (pintype "passive"))
      (node (ref "REG5") (pin "2") (pinfunction "OUT_2") (pintype "passive"))
      (node (ref "U5") (pin "10") (pinfunction "VS+_10") (pintype "passive"))
      (node (ref "U6") (pin "10") (pinfunction "VS+_10") (pintype "passive"))
    )
    (net (code "131") (name "/VSS1") (class "Default")
      (node (ref "D5") (pin "1") (pinfunction "anodo_1") (pintype "passive"))
      (node (ref "LED8") (pin "2") (pinfunction "2_2") (pintype "passive"))
      (node (ref "OPT2") (pin "4") (pinfunction "EMIT_4") (pintype "passive"))
      (node (ref "P5") (pin "2") (pinfunction "2_2") (pintype "passive"))
      (node (ref "P5") (pin "4") (pinfunction "4_4") (pintype "passive"))
      (node (ref "R62") (pin "1") (pinfunction "1_1") (pintype "passive"))
      (node (ref "U1") (pin "1") (pinfunction "V-_1") (pintype "passive"))
      (node (ref "U1") (pin "10") (pinfunction "V-_10") (pintype "passive"))
      (node (ref "U1") (pin "11") (pinfunction "V-_11") (pintype "passive"))
      (node (ref "U1") (pin "13") (pinfunction "V-PWR_13") (pintype "passive"))
      (node (ref "U1") (pin "14") (pinfunction "V-PWR_14") (pintype "passive"))
      (node (ref "U1") (pin "20") (pinfunction "V-_20") (pintype "passive"))
      (node (ref "U1") (pin "21") (pinfunction "V-_21") (pintype "passive"))
    )
    (net (code "132") (name "/VSS2") (class "Default")
      (node (ref "D6") (pin "1") (pinfunction "anodo_1") (pintype "passive"))
      (node (ref "LED7") (pin "2") (pinfunction "2_2") (pintype "passive"))
      (node (ref "OPT1") (pin "4") (pinfunction "EMIT_4") (pintype "passive"))
      (node (ref "P6") (pin "2") (pinfunction "2_2") (pintype "passive"))
      (node (ref "P6") (pin "4") (pinfunction "4_4") (pintype "passive"))
      (node (ref "R67") (pin "1") (pinfunction "1_1") (pintype "passive"))
      (node (ref "U2") (pin "1") (pinfunction "V-_1") (pintype "passive"))
      (node (ref "U2") (pin "10") (pinfunction "V-_10") (pintype "passive"))
      (node (ref "U2") (pin "11") (pinfunction "V-_11") (pintype "passive"))
      (node (ref "U2") (pin "13") (pinfunction "V-PWR_13") (pintype "passive"))
      (node (ref "U2") (pin "14") (pinfunction "V-PWR_14") (pintype "passive"))
      (node (ref "U2") (pin "20") (pinfunction "V-_20") (pintype "passive"))
      (node (ref "U2") (pin "21") (pinfunction "V-_21") (pintype "passive"))
    )
    (net (code "133") (name "/VSS3") (class "Default")
      (node (ref "D7") (pin "1") (pinfunction "anodo_1") (pintype "passive"))
      (node (ref "LED6") (pin "2") (pinfunction "2_2") (pintype "passive"))
      (node (ref "OPT4") (pin "4") (pinfunction "EMIT_4") (pintype "passive"))
      (node (ref "P7") (pin "2") (pinfunction "2_2") (pintype "passive"))
      (node (ref "P7") (pin "4") (pinfunction "4_4") (pintype "passive"))
      (node (ref "R72") (pin "1") (pinfunction "1_1") (pintype "passive"))
      (node (ref "U3") (pin "1") (pinfunction "V-_1") (pintype "passive"))
      (node (ref "U3") (pin "10") (pinfunction "V-_10") (pintype "passive"))
      (node (ref "U3") (pin "11") (pinfunction "V-_11") (pintype "passive"))
      (node (ref "U3") (pin "13") (pinfunction "V-PWR_13") (pintype "passive"))
      (node (ref "U3") (pin "14") (pinfunction "V-PWR_14") (pintype "passive"))
      (node (ref "U3") (pin "20") (pinfunction "V-_20") (pintype "passive"))
      (node (ref "U3") (pin "21") (pinfunction "V-_21") (pintype "passive"))
    )
    (net (code "134") (name "/VSS4") (class "Default")
      (node (ref "D8") (pin "1") (pinfunction "anodo_1") (pintype "passive"))
      (node (ref "LED5") (pin "2") (pinfunction "2_2") (pintype "passive"))
      (node (ref "OPT3") (pin "4") (pinfunction "EMIT_4") (pintype "passive"))
      (node (ref "P8") (pin "2") (pinfunction "2_2") (pintype "passive"))
      (node (ref "P8") (pin "4") (pinfunction "4_4") (pintype "passive"))
      (node (ref "R77") (pin "1") (pinfunction "1_1") (pintype "passive"))
      (node (ref "U4") (pin "1") (pinfunction "V-_1") (pintype "passive"))
      (node (ref "U4") (pin "10") (pinfunction "V-_10") (pintype "passive"))
      (node (ref "U4") (pin "11") (pinfunction "V-_11") (pintype "passive"))
      (node (ref "U4") (pin "13") (pinfunction "V-PWR_13") (pintype "passive"))
      (node (ref "U4") (pin "14") (pinfunction "V-PWR_14") (pintype "passive"))
      (node (ref "U4") (pin "20") (pinfunction "V-_20") (pintype "passive"))
      (node (ref "U4") (pin "21") (pinfunction "V-_21") (pintype "passive"))
    )
    (net (code "135") (name "/VSSR") (class "Default")
      (node (ref "OPT5") (pin "4") (pinfunction "EMIT_4") (pintype "passive"))
      (node (ref "OPT6") (pin "4") (pinfunction "EMIT_4") (pintype "passive"))
      (node (ref "OPT7") (pin "4") (pinfunction "EMIT_4") (pintype "passive"))
      (node (ref "OPT8") (pin "4") (pinfunction "EMIT_4") (pintype "passive"))
      (node (ref "P4") (pin "2") (pinfunction "2_2") (pintype "passive"))
      (node (ref "P4") (pin "4") (pinfunction "4_4") (pintype "passive"))
      (node (ref "P4") (pin "6") (pinfunction "6_6") (pintype "passive"))
      (node (ref "U5") (pin "11") (pinfunction "GND_11") (pintype "passive"))
      (node (ref "U5") (pin "4") (pinfunction "VS-_4") (pintype "passive"))
      (node (ref "U6") (pin "11") (pinfunction "GND_11") (pintype "passive"))
      (node (ref "U6") (pin "4") (pinfunction "VS-_4") (pintype "passive"))
    )
    (net (code "136") (name "Net-(D5-cátodo)") (class "Default")
      (node (ref "D5") (pin "2") (pinfunction "cátodo_2") (pintype "passive"))
      (node (ref "R250") (pin "2") (pinfunction "2_2") (pintype "passive"))
      (node (ref "U1") (pin "7") (pinfunction "VDIG_7") (pintype "passive"))
    )
    (net (code "137") (name "Net-(D6-cátodo)") (class "Default")
      (node (ref "D6") (pin "2") (pinfunction "cátodo_2") (pintype "passive"))
      (node (ref "R256") (pin "2") (pinfunction "2_2") (pintype "passive"))
      (node (ref "U2") (pin "7") (pinfunction "VDIG_7") (pintype "passive"))
    )
    (net (code "138") (name "Net-(D7-cátodo)") (class "Default")
      (node (ref "D7") (pin "2") (pinfunction "cátodo_2") (pintype "passive"))
      (node (ref "R261") (pin "2") (pinfunction "2_2") (pintype "passive"))
      (node (ref "U3") (pin "7") (pinfunction "VDIG_7") (pintype "passive"))
    )
    (net (code "139") (name "Net-(D8-cátodo)") (class "Default")
      (node (ref "D8") (pin "2") (pinfunction "cátodo_2") (pintype "passive"))
      (node (ref "R265") (pin "2") (pinfunction "2_2") (pintype "passive"))
      (node (ref "U4") (pin "7") (pinfunction "VDIG_7") (pintype "passive"))
    )
    (net (code "140") (name "Net-(LED1-Pad1)") (class "Default")
      (node (ref "LED1") (pin "1") (pinfunction "1_1") (pintype "passive"))
      (node (ref "R1") (pin "2") (pinfunction "2_2") (pintype "passive"))
    )
    (net (code "141") (name "Net-(LED2-Pad1)") (class "Default")
      (node (ref "LED2") (pin "1") (pinfunction "1_1") (pintype "passive"))
      (node (ref "R2") (pin "2") (pinfunction "2_2") (pintype "passive"))
    )
    (net (code "142") (name "Net-(LED3-Pad1)") (class "Default")
      (node (ref "LED3") (pin "1") (pinfunction "1_1") (pintype "passive"))
      (node (ref "R3") (pin "2") (pinfunction "2_2") (pintype "passive"))
    )
    (net (code "143") (name "Net-(LED4-Pad1)") (class "Default")
      (node (ref "LED4") (pin "1") (pinfunction "1_1") (pintype "passive"))
      (node (ref "R4") (pin "2") (pinfunction "2_2") (pintype "passive"))
    )
    (net (code "144") (name "Net-(LED5-Pad1)") (class "Default")
      (node (ref "LED5") (pin "1") (pinfunction "1_1") (pintype "passive"))
      (node (ref "R5") (pin "2") (pinfunction "2_2") (pintype "passive"))
    )
    (net (code "145") (name "Net-(LED6-Pad1)") (class "Default")
      (node (ref "LED6") (pin "1") (pinfunction "1_1") (pintype "passive"))
      (node (ref "R6") (pin "2") (pinfunction "2_2") (pintype "passive"))
    )
    (net (code "146") (name "Net-(LED7-Pad1)") (class "Default")
      (node (ref "LED7") (pin "1") (pinfunction "1_1") (pintype "passive"))
      (node (ref "R7") (pin "2") (pinfunction "2_2") (pintype "passive"))
    )
    (net (code "147") (name "Net-(LED8-Pad1)") (class "Default")
      (node (ref "LED8") (pin "1") (pinfunction "1_1") (pintype "passive"))
      (node (ref "R8") (pin "2") (pinfunction "2_2") (pintype "passive"))
    )
    (net (code "148") (name "Net-(OPT1-AN)") (class "Default")
      (node (ref "OPT1") (pin "1") (pinfunction "AN_1") (pintype "passive"))
      (node (ref "R230") (pin "2") (pinfunction "2_2") (pintype "passive"))
    )
    (net (code "149") (name "Net-(OPT2-AN)") (class "Default")
      (node (ref "OPT2") (pin "1") (pinfunction "AN_1") (pintype "passive"))
      (node (ref "R235") (pin "2") (pinfunction "2_2") (pintype "passive"))
    )
    (net (code "150") (name "Net-(OPT3-AN)") (class "Default")
      (node (ref "OPT3") (pin "1") (pinfunction "AN_1") (pintype "passive"))
      (node (ref "R240") (pin "2") (pinfunction "2_2") (pintype "passive"))
    )
    (net (code "151") (name "Net-(OPT4-AN)") (class "Default")
      (node (ref "OPT4") (pin "1") (pinfunction "AN_1") (pintype "passive"))
      (node (ref "R245") (pin "2") (pinfunction "2_2") (pintype "passive"))
    )
    (net (code "152") (name "Net-(OPT5-AN)") (class "Default")
      (node (ref "OPT5") (pin "1") (pinfunction "AN_1") (pintype "passive"))
      (node (ref "R269") (pin "2") (pinfunction "2_2") (pintype "passive"))
    )
    (net (code "153") (name "Net-(OPT6-AN)") (class "Default")
      (node (ref "OPT6") (pin "1") (pinfunction "AN_1") (pintype "passive"))
      (node (ref "R369") (pin "2") (pinfunction "2_2") (pintype "passive"))
    )
    (net (code "154") (name "Net-(OPT7-AN)") (class "Default")
      (node (ref "OPT7") (pin "1") (pinfunction "AN_1") (pintype "passive"))
      (node (ref "R371") (pin "2") (pinfunction "2_2") (pintype "passive"))
    )
    (net (code "155") (name "Net-(OPT8-AN)") (class "Default")
      (node (ref "OPT8") (pin "1") (pinfunction "AN_1") (pintype "passive"))
      (node (ref "R373") (pin "2") (pinfunction "2_2") (pintype "passive"))
    )
    (net (code "156") (name "Net-(P9-Pad3)") (class "Default")
      (node (ref "P9") (pin "3") (pinfunction "3_3") (pintype "passive"))
      (node (ref "R66") (pin "1") (pinfunction "1_1") (pintype "passive"))
    )
    (net (code "157") (name "Net-(P9-Pad5)") (class "Default")
      (node (ref "P9") (pin "5") (pinfunction "5_5") (pintype "passive"))
      (node (ref "R65") (pin "1") (pinfunction "1_1") (pintype "passive"))
    )
    (net (code "158") (name "Net-(P9-Pad7)") (class "Default")
      (node (ref "P9") (pin "7") (pinfunction "7_7") (pintype "passive"))
      (node (ref "R64") (pin "1") (pinfunction "1_1") (pintype "passive"))
    )
    (net (code "159") (name "Net-(P9-Pad9)") (class "Default")
      (node (ref "P9") (pin "9") (pinfunction "9_9") (pintype "passive"))
      (node (ref "R63") (pin "1") (pinfunction "1_1") (pintype "passive"))
    )
    (net (code "160") (name "Net-(P10-Pad3)") (class "Default")
      (node (ref "P10") (pin "3") (pinfunction "3_3") (pintype "passive"))
      (node (ref "R71") (pin "1") (pinfunction "1_1") (pintype "passive"))
    )
    (net (code "161") (name "Net-(P10-Pad5)") (class "Default")
      (node (ref "P10") (pin "5") (pinfunction "5_5") (pintype "passive"))
      (node (ref "R70") (pin "1") (pinfunction "1_1") (pintype "passive"))
    )
    (net (code "162") (name "Net-(P10-Pad7)") (class "Default")
      (node (ref "P10") (pin "7") (pinfunction "7_7") (pintype "passive"))
      (node (ref "R69") (pin "1") (pinfunction "1_1") (pintype "passive"))
    )
    (net (code "163") (name "Net-(P10-Pad9)") (class "Default")
      (node (ref "P10") (pin "9") (pinfunction "9_9") (pintype "passive"))
      (node (ref "R68") (pin "1") (pinfunction "1_1") (pintype "passive"))
    )
    (net (code "164") (name "Net-(P11-Pad3)") (class "Default")
      (node (ref "P11") (pin "3") (pinfunction "3_3") (pintype "passive"))
      (node (ref "R76") (pin "1") (pinfunction "1_1") (pintype "passive"))
    )
    (net (code "165") (name "Net-(P11-Pad5)") (class "Default")
      (node (ref "P11") (pin "5") (pinfunction "5_5") (pintype "passive"))
      (node (ref "R75") (pin "1") (pinfunction "1_1") (pintype "passive"))
    )
    (net (code "166") (name "Net-(P11-Pad7)") (class "Default")
      (node (ref "P11") (pin "7") (pinfunction "7_7") (pintype "passive"))
      (node (ref "R74") (pin "1") (pinfunction "1_1") (pintype "passive"))
    )
    (net (code "167") (name "Net-(P11-Pad9)") (class "Default")
      (node (ref "P11") (pin "9") (pinfunction "9_9") (pintype "passive"))
      (node (ref "R73") (pin "1") (pinfunction "1_1") (pintype "passive"))
    )
    (net (code "168") (name "Net-(P12-Pad3)") (class "Default")
      (node (ref "P12") (pin "3") (pinfunction "3_3") (pintype "passive"))
      (node (ref "R81") (pin "1") (pinfunction "1_1") (pintype "passive"))
    )
    (net (code "169") (name "Net-(P12-Pad5)") (class "Default")
      (node (ref "P12") (pin "5") (pinfunction "5_5") (pintype "passive"))
      (node (ref "R80") (pin "1") (pinfunction "1_1") (pintype "passive"))
    )
    (net (code "170") (name "Net-(P12-Pad7)") (class "Default")
      (node (ref "P12") (pin "7") (pinfunction "7_7") (pintype "passive"))
      (node (ref "R79") (pin "1") (pinfunction "1_1") (pintype "passive"))
    )
    (net (code "171") (name "Net-(P12-Pad9)") (class "Default")
      (node (ref "P12") (pin "9") (pinfunction "9_9") (pintype "passive"))
      (node (ref "R78") (pin "1") (pinfunction "1_1") (pintype "passive"))
    )
    (net (code "172") (name "Net-(P13-Pad3)") (class "Default")
      (node (ref "P13") (pin "3") (pinfunction "3_3") (pintype "passive"))
      (node (ref "R85") (pin "1") (pinfunction "1_1") (pintype "passive"))
    )
    (net (code "173") (name "Net-(P13-Pad5)") (class "Default")
      (node (ref "P13") (pin "5") (pinfunction "5_5") (pintype "passive"))
      (node (ref "R84") (pin "1") (pinfunction "1_1") (pintype "passive"))
    )
    (net (code "174") (name "Net-(P13-Pad7)") (class "Default")
      (node (ref "P13") (pin "7") (pinfunction "7_7") (pintype "passive"))
      (node (ref "R83") (pin "1") (pinfunction "1_1") (pintype "passive"))
    )
    (net (code "175") (name "Net-(P13-Pad9)") (class "Default")
      (node (ref "P13") (pin "9") (pinfunction "9_9") (pintype "passive"))
      (node (ref "R82") (pin "1") (pinfunction "1_1") (pintype "passive"))
    )
    (net (code "176") (name "Net-(P14-Pad3)") (class "Default")
      (node (ref "P14") (pin "3") (pinfunction "3_3") (pintype "passive"))
      (node (ref "R89") (pin "1") (pinfunction "1_1") (pintype "passive"))
    )
    (net (code "177") (name "Net-(P14-Pad5)") (class "Default")
      (node (ref "P14") (pin "5") (pinfunction "5_5") (pintype "passive"))
      (node (ref "R88") (pin "1") (pinfunction "1_1") (pintype "passive"))
    )
    (net (code "178") (name "Net-(P14-Pad7)") (class "Default")
      (node (ref "P14") (pin "7") (pinfunction "7_7") (pintype "passive"))
      (node (ref "R87") (pin "1") (pinfunction "1_1") (pintype "passive"))
    )
    (net (code "179") (name "Net-(P14-Pad9)") (class "Default")
      (node (ref "P14") (pin "9") (pinfunction "9_9") (pintype "passive"))
      (node (ref "R86") (pin "1") (pinfunction "1_1") (pintype "passive"))
    )
    (net (code "180") (name "Net-(P15-Pad3)") (class "Default")
      (node (ref "P15") (pin "3") (pinfunction "3_3") (pintype "passive"))
      (node (ref "R93") (pin "1") (pinfunction "1_1") (pintype "passive"))
    )
    (net (code "181") (name "Net-(P15-Pad5)") (class "Default")
      (node (ref "P15") (pin "5") (pinfunction "5_5") (pintype "passive"))
      (node (ref "R92") (pin "1") (pinfunction "1_1") (pintype "passive"))
    )
    (net (code "182") (name "Net-(P15-Pad7)") (class "Default")
      (node (ref "P15") (pin "7") (pinfunction "7_7") (pintype "passive"))
      (node (ref "R91") (pin "1") (pinfunction "1_1") (pintype "passive"))
    )
    (net (code "183") (name "Net-(P15-Pad9)") (class "Default")
      (node (ref "P15") (pin "9") (pinfunction "9_9") (pintype "passive"))
      (node (ref "R90") (pin "1") (pinfunction "1_1") (pintype "passive"))
    )
    (net (code "184") (name "Net-(P16-Pad3)") (class "Default")
      (node (ref "P16") (pin "3") (pinfunction "3_3") (pintype "passive"))
      (node (ref "R97") (pin "1") (pinfunction "1_1") (pintype "passive"))
    )
    (net (code "185") (name "Net-(P16-Pad5)") (class "Default")
      (node (ref "P16") (pin "5") (pinfunction "5_5") (pintype "passive"))
      (node (ref "R96") (pin "1") (pinfunction "1_1") (pintype "passive"))
    )
    (net (code "186") (name "Net-(P16-Pad7)") (class "Default")
      (node (ref "P16") (pin "7") (pinfunction "7_7") (pintype "passive"))
      (node (ref "R95") (pin "1") (pinfunction "1_1") (pintype "passive"))
    )
    (net (code "187") (name "Net-(P16-Pad9)") (class "Default")
      (node (ref "P16") (pin "9") (pinfunction "9_9") (pintype "passive"))
      (node (ref "R94") (pin "1") (pinfunction "1_1") (pintype "passive"))
    )
    (net (code "188") (name "Net-(R17-Pad1)") (class "Default")
      (node (ref "R17") (pin "1") (pinfunction "1_1") (pintype "passive"))
      (node (ref "R18") (pin "1") (pinfunction "1_1") (pintype "passive"))
    )
    (net (code "189") (name "Net-(R23-Pad1)") (class "Default")
      (node (ref "R23") (pin "1") (pinfunction "1_1") (pintype "passive"))
      (node (ref "R24") (pin "1") (pinfunction "1_1") (pintype "passive"))
    )
    (net (code "190") (name "Net-(R29-Pad1)") (class "Default")
      (node (ref "R29") (pin "1") (pinfunction "1_1") (pintype "passive"))
      (node (ref "R30") (pin "1") (pinfunction "1_1") (pintype "passive"))
    )
    (net (code "191") (name "Net-(R35-Pad1)") (class "Default")
      (node (ref "R35") (pin "1") (pinfunction "1_1") (pintype "passive"))
      (node (ref "R36") (pin "1") (pinfunction "1_1") (pintype "passive"))
    )
    (net (code "192") (name "Net-(R41-Pad1)") (class "Default")
      (node (ref "R41") (pin "1") (pinfunction "1_1") (pintype "passive"))
      (node (ref "R42") (pin "1") (pinfunction "1_1") (pintype "passive"))
    )
    (net (code "193") (name "Net-(R47-Pad1)") (class "Default")
      (node (ref "R47") (pin "1") (pinfunction "1_1") (pintype "passive"))
      (node (ref "R48") (pin "1") (pinfunction "1_1") (pintype "passive"))
    )
    (net (code "194") (name "Net-(R53-Pad1)") (class "Default")
      (node (ref "R53") (pin "1") (pinfunction "1_1") (pintype "passive"))
      (node (ref "R54") (pin "1") (pinfunction "1_1") (pintype "passive"))
    )
    (net (code "195") (name "Net-(R59-Pad1)") (class "Default")
      (node (ref "R59") (pin "1") (pinfunction "1_1") (pintype "passive"))
      (node (ref "R60") (pin "1") (pinfunction "1_1") (pintype "passive"))
    )
    (net (code "196") (name "Net-(RPOT1-b)") (class "Default")
      (node (ref "R9") (pin "2") (pinfunction "2_2") (pintype "passive"))
      (node (ref "RPOT1") (pin "2") (pinfunction "b_2") (pintype "passive"))
    )
    (net (code "197") (name "Net-(RPOT2-b)") (class "Default")
      (node (ref "R10") (pin "2") (pinfunction "2_2") (pintype "passive"))
      (node (ref "RPOT2") (pin "2") (pinfunction "b_2") (pintype "passive"))
    )
    (net (code "198") (name "Net-(RPOT3-b)") (class "Default")
      (node (ref "R11") (pin "2") (pinfunction "2_2") (pintype "passive"))
      (node (ref "RPOT3") (pin "2") (pinfunction "b_2") (pintype "passive"))
    )
    (net (code "199") (name "Net-(RPOT4-b)") (class "Default")
      (node (ref "R12") (pin "2") (pinfunction "2_2") (pintype "passive"))
      (node (ref "RPOT4") (pin "2") (pinfunction "b_2") (pintype "passive"))
    )
    (net (code "200") (name "Net-(RPOT5-b)") (class "Default")
      (node (ref "R13") (pin "2") (pinfunction "2_2") (pintype "passive"))
      (node (ref "RPOT5") (pin "2") (pinfunction "b_2") (pintype "passive"))
    )
    (net (code "201") (name "unconnected-(DPOT1-A1-Pad2)") (class "Default")
      (node (ref "DPOT1") (pin "2") (pinfunction "A1_2") (pintype "passive+no_connect"))
    )
    (net (code "202") (name "unconnected-(DPOT2-A1-Pad2)") (class "Default")
      (node (ref "DPOT2") (pin "2") (pinfunction "A1_2") (pintype "passive+no_connect"))
    )
    (net (code "203") (name "unconnected-(DPOT3-A1-Pad2)") (class "Default")
      (node (ref "DPOT3") (pin "2") (pinfunction "A1_2") (pintype "passive+no_connect"))
    )
    (net (code "204") (name "unconnected-(DPOT3-B2-Pad9)") (class "Default")
      (node (ref "DPOT3") (pin "9") (pinfunction "B2_9") (pintype "passive+no_connect"))
    )
    (net (code "205") (name "unconnected-(DPOT3-W2-Pad3)") (class "Default")
      (node (ref "DPOT3") (pin "3") (pinfunction "W2_3") (pintype "passive+no_connect"))
    )
    (net (code "206") (name "unconnected-(OPT1-BASE-Pad6)") (class "Default")
      (node (ref "OPT1") (pin "6") (pinfunction "BASE_6") (pintype "passive+no_connect"))
    )
    (net (code "207") (name "unconnected-(OPT1-NC-Pad3)") (class "Default")
      (node (ref "OPT1") (pin "3") (pinfunction "NC_3") (pintype "passive+no_connect"))
    )
    (net (code "208") (name "unconnected-(OPT2-BASE-Pad6)") (class "Default")
      (node (ref "OPT2") (pin "6") (pinfunction "BASE_6") (pintype "passive+no_connect"))
    )
    (net (code "209") (name "unconnected-(OPT2-NC-Pad3)") (class "Default")
      (node (ref "OPT2") (pin "3") (pinfunction "NC_3") (pintype "passive+no_connect"))
    )
    (net (code "210") (name "unconnected-(OPT3-BASE-Pad6)") (class "Default")
      (node (ref "OPT3") (pin "6") (pinfunction "BASE_6") (pintype "passive+no_connect"))
    )
    (net (code "211") (name "unconnected-(OPT3-NC-Pad3)") (class "Default")
      (node (ref "OPT3") (pin "3") (pinfunction "NC_3") (pintype "passive+no_connect"))
    )
    (net (code "212") (name "unconnected-(OPT4-BASE-Pad6)") (class "Default")
      (node (ref "OPT4") (pin "6") (pinfunction "BASE_6") (pintype "passive+no_connect"))
    )
    (net (code "213") (name "unconnected-(OPT4-NC-Pad3)") (class "Default")
      (node (ref "OPT4") (pin "3") (pinfunction "NC_3") (pintype "passive+no_connect"))
    )
    (net (code "214") (name "unconnected-(OPT5-BASE-Pad6)") (class "Default")
      (node (ref "OPT5") (pin "6") (pinfunction "BASE_6") (pintype "passive+no_connect"))
    )
    (net (code "215") (name "unconnected-(OPT5-NC-Pad3)") (class "Default")
      (node (ref "OPT5") (pin "3") (pinfunction "NC_3") (pintype "passive+no_connect"))
    )
    (net (code "216") (name "unconnected-(OPT6-BASE-Pad6)") (class "Default")
      (node (ref "OPT6") (pin "6") (pinfunction "BASE_6") (pintype "passive+no_connect"))
    )
    (net (code "217") (name "unconnected-(OPT6-NC-Pad3)") (class "Default")
      (node (ref "OPT6") (pin "3") (pinfunction "NC_3") (pintype "passive+no_connect"))
    )
    (net (code "218") (name "unconnected-(OPT7-BASE-Pad6)") (class "Default")
      (node (ref "OPT7") (pin "6") (pinfunction "BASE_6") (pintype "passive+no_connect"))
    )
    (net (code "219") (name "unconnected-(OPT7-NC-Pad3)") (class "Default")
      (node (ref "OPT7") (pin "3") (pinfunction "NC_3") (pintype "passive+no_connect"))
    )
    (net (code "220") (name "unconnected-(OPT8-BASE-Pad6)") (class "Default")
      (node (ref "OPT8") (pin "6") (pinfunction "BASE_6") (pintype "passive+no_connect"))
    )
    (net (code "221") (name "unconnected-(OPT8-NC-Pad3)") (class "Default")
      (node (ref "OPT8") (pin "3") (pinfunction "NC_3") (pintype "passive+no_connect"))
    )
    (net (code "222") (name "unconnected-(RPOT1-c-Pad3)") (class "Default")
      (node (ref "RPOT1") (pin "3") (pinfunction "c_3") (pintype "passive+no_connect"))
    )
    (net (code "223") (name "unconnected-(RPOT2-c-Pad3)") (class "Default")
      (node (ref "RPOT2") (pin "3") (pinfunction "c_3") (pintype "passive+no_connect"))
    )
    (net (code "224") (name "unconnected-(RPOT3-c-Pad3)") (class "Default")
      (node (ref "RPOT3") (pin "3") (pinfunction "c_3") (pintype "passive+no_connect"))
    )
    (net (code "225") (name "unconnected-(RPOT4-c-Pad3)") (class "Default")
      (node (ref "RPOT4") (pin "3") (pinfunction "c_3") (pintype "passive+no_connect"))
    )
    (net (code "226") (name "unconnected-(RPOT5-c-Pad3)") (class "Default")
      (node (ref "RPOT5") (pin "3") (pinfunction "c_3") (pintype "passive+no_connect"))
    )
    (net (code "227") (name "unconnected-(U1-TSENSE-Pad12)") (class "Default")
      (node (ref "U1") (pin "12") (pinfunction "TSENSE_12") (pintype "passive+no_connect"))
    )
    (net (code "228") (name "unconnected-(U2-TSENSE-Pad12)") (class "Default")
      (node (ref "U2") (pin "12") (pinfunction "TSENSE_12") (pintype "passive+no_connect"))
    )
    (net (code "229") (name "unconnected-(U3-TSENSE-Pad12)") (class "Default")
      (node (ref "U3") (pin "12") (pinfunction "TSENSE_12") (pintype "passive+no_connect"))
    )
    (net (code "230") (name "unconnected-(U4-TSENSE-Pad12)") (class "Default")
      (node (ref "U4") (pin "12") (pinfunction "TSENSE_12") (pintype "passive+no_connect"))
    )
  )
)
